# DIY_Keyboard_V1_4.net
KiCad netlist of a schematic drawn in EAGLE
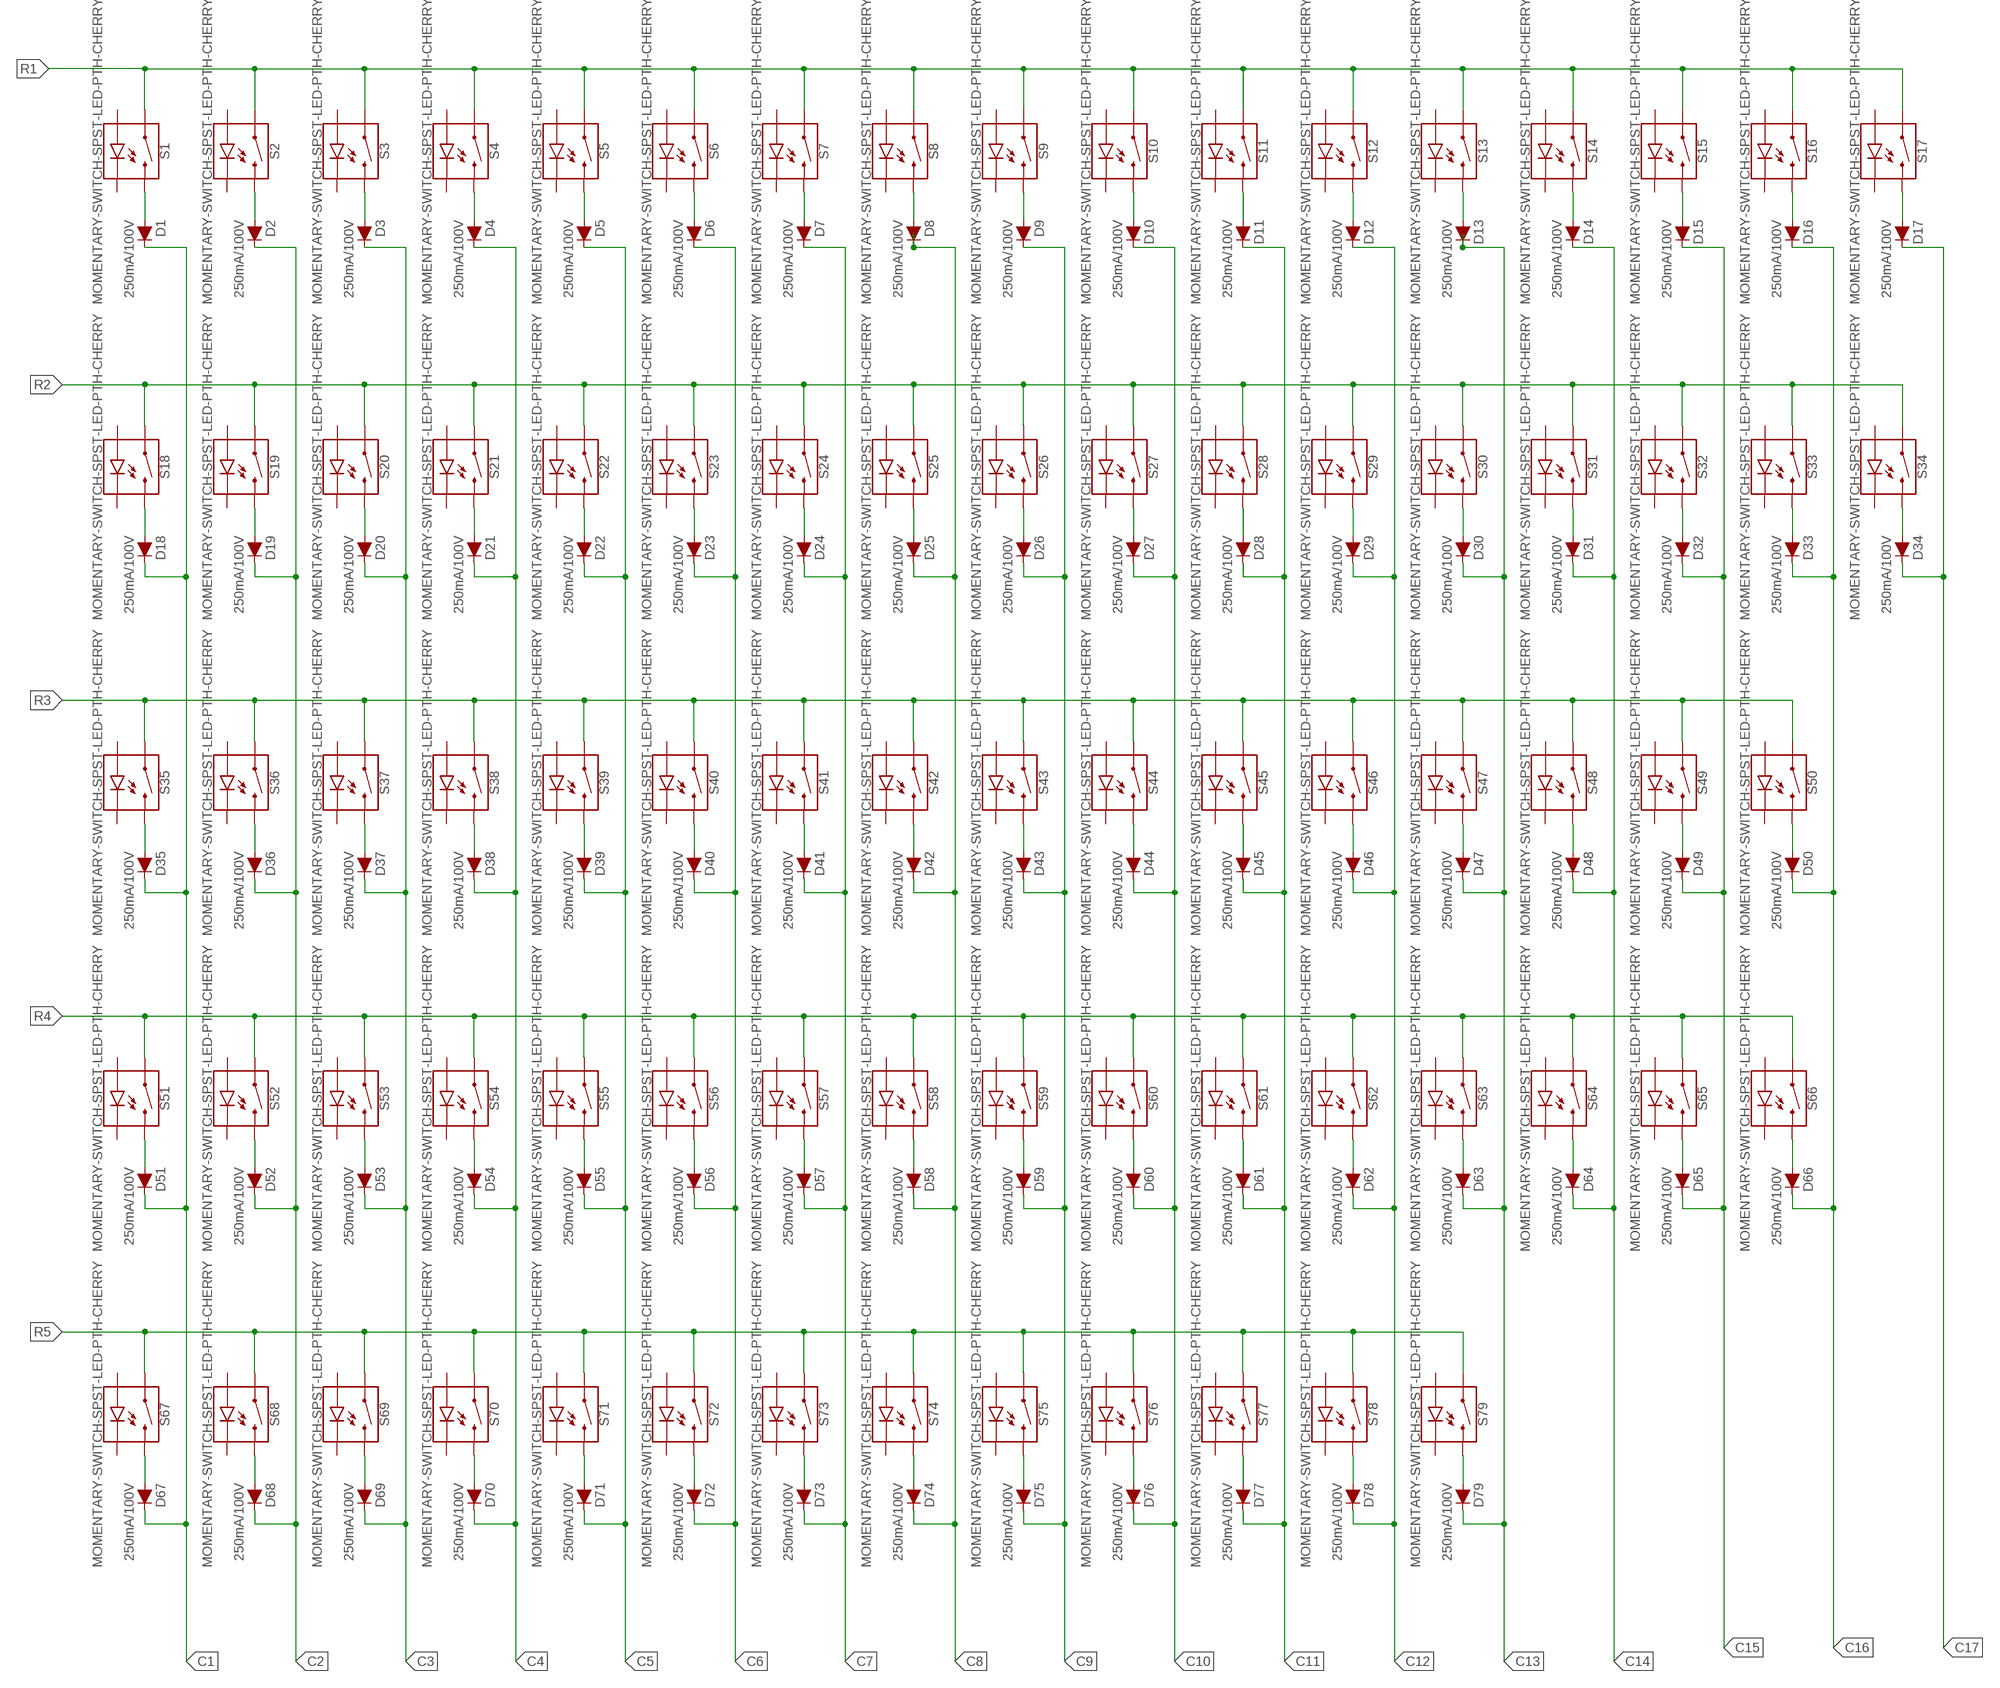
[diagram p0: schematic, sheet 1, part 1 of 2]
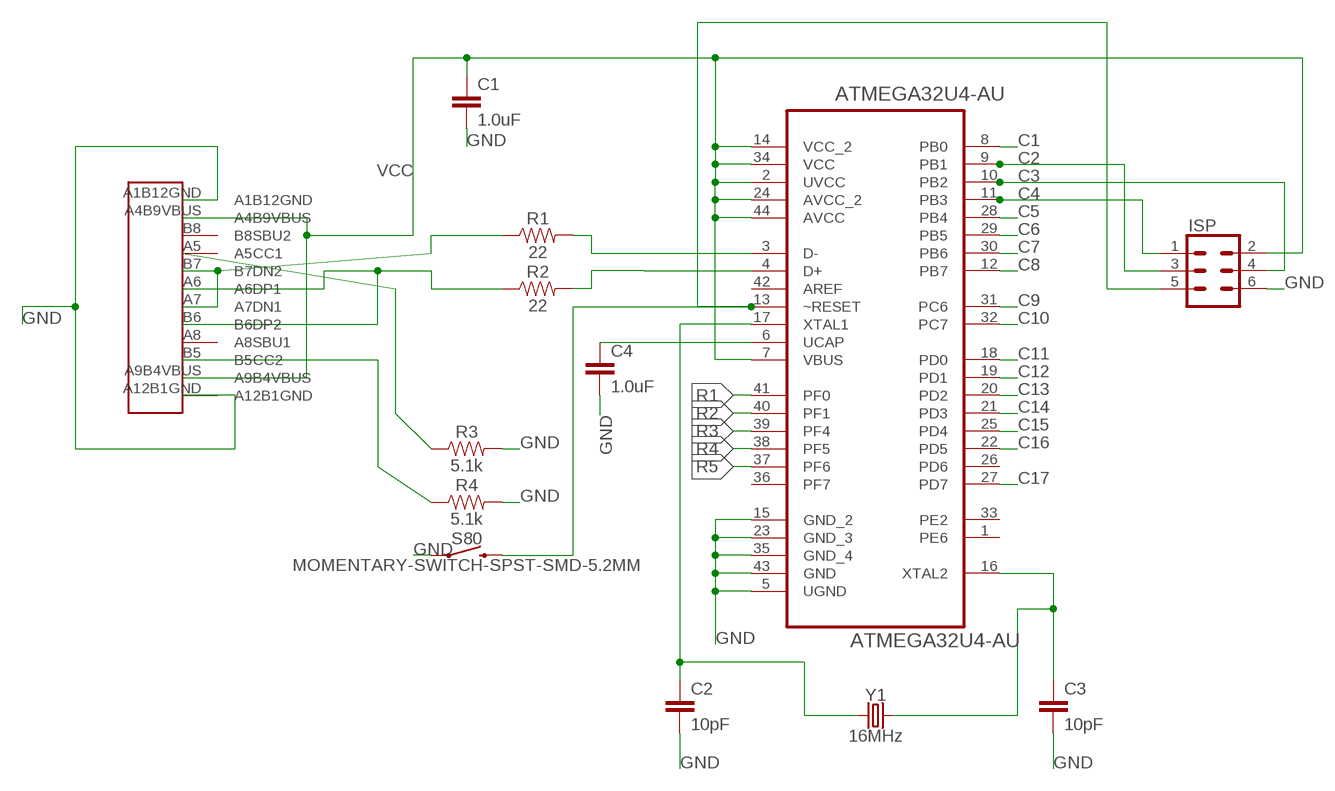
[diagram p1: schematic, sheet 1, part 2 of 2]

(export (version "E")
  (design (tool "Eeschema 10.0.6"))
  (components
    (comp (ref "ATMEGA32U4-AU")
      (value "ATMEGA32U4-AU")
      (footprint "eagle-import:QFP80P1200X1200X120-44N")
      (fields (field (name "MF") "Microchip"))
      (libsource (lib "eagle-import") (part "ATMEGA32U4-AU"))
    )
    (comp (ref "C1")
      (value "1.0uF")
      (footprint "eagle-import:0603")
      (libsource (lib "eagle-import") (part "1.0UF-0603-16V-10%"))
    )
    (comp (ref "C2")
      (value "10pF")
      (footprint "eagle-import:0603")
      (libsource (lib "eagle-import") (part "10PF-0603-50V-5%"))
    )
    (comp (ref "C3")
      (value "10pF")
      (footprint "eagle-import:0603")
      (libsource (lib "eagle-import") (part "10PF-0603-50V-5%"))
    )
    (comp (ref "C4")
      (value "1.0uF")
      (footprint "eagle-import:0603")
      (libsource (lib "eagle-import") (part "1.0UF-0603-16V-10%"))
    )
    (comp (ref "D1")
      (value "250mA/100V")
      (footprint "eagle-import:SOD-323")
      (libsource (lib "eagle-import") (part "DIODE-BAS16J"))
    )
    (comp (ref "D2")
      (value "250mA/100V")
      (footprint "eagle-import:SOD-323")
      (libsource (lib "eagle-import") (part "DIODE-BAS16J"))
    )
    (comp (ref "D3")
      (value "250mA/100V")
      (footprint "eagle-import:SOD-323")
      (libsource (lib "eagle-import") (part "DIODE-BAS16J"))
    )
    (comp (ref "D4")
      (value "250mA/100V")
      (footprint "eagle-import:SOD-323")
      (libsource (lib "eagle-import") (part "DIODE-BAS16J"))
    )
    (comp (ref "D5")
      (value "250mA/100V")
      (footprint "eagle-import:SOD-323")
      (libsource (lib "eagle-import") (part "DIODE-BAS16J"))
    )
    (comp (ref "D6")
      (value "250mA/100V")
      (footprint "eagle-import:SOD-323")
      (libsource (lib "eagle-import") (part "DIODE-BAS16J"))
    )
    (comp (ref "D7")
      (value "250mA/100V")
      (footprint "eagle-import:SOD-323")
      (libsource (lib "eagle-import") (part "DIODE-BAS16J"))
    )
    (comp (ref "D8")
      (value "250mA/100V")
      (footprint "eagle-import:SOD-323")
      (libsource (lib "eagle-import") (part "DIODE-BAS16J"))
    )
    (comp (ref "D9")
      (value "250mA/100V")
      (footprint "eagle-import:SOD-323")
      (libsource (lib "eagle-import") (part "DIODE-BAS16J"))
    )
    (comp (ref "D10")
      (value "250mA/100V")
      (footprint "eagle-import:SOD-323")
      (libsource (lib "eagle-import") (part "DIODE-BAS16J"))
    )
    (comp (ref "D11")
      (value "250mA/100V")
      (footprint "eagle-import:SOD-323")
      (libsource (lib "eagle-import") (part "DIODE-BAS16J"))
    )
    (comp (ref "D12")
      (value "250mA/100V")
      (footprint "eagle-import:SOD-323")
      (libsource (lib "eagle-import") (part "DIODE-BAS16J"))
    )
    (comp (ref "D13")
      (value "250mA/100V")
      (footprint "eagle-import:SOD-323")
      (libsource (lib "eagle-import") (part "DIODE-BAS16J"))
    )
    (comp (ref "D14")
      (value "250mA/100V")
      (footprint "eagle-import:SOD-323")
      (libsource (lib "eagle-import") (part "DIODE-BAS16J"))
    )
    (comp (ref "D15")
      (value "250mA/100V")
      (footprint "eagle-import:SOD-323")
      (libsource (lib "eagle-import") (part "DIODE-BAS16J"))
    )
    (comp (ref "D16")
      (value "250mA/100V")
      (footprint "eagle-import:SOD-323")
      (libsource (lib "eagle-import") (part "DIODE-BAS16J"))
    )
    (comp (ref "D17")
      (value "250mA/100V")
      (footprint "eagle-import:SOD-323")
      (libsource (lib "eagle-import") (part "DIODE-BAS16J"))
    )
    (comp (ref "D18")
      (value "250mA/100V")
      (footprint "eagle-import:SOD-323")
      (libsource (lib "eagle-import") (part "DIODE-BAS16J"))
    )
    (comp (ref "D19")
      (value "250mA/100V")
      (footprint "eagle-import:SOD-323")
      (libsource (lib "eagle-import") (part "DIODE-BAS16J"))
    )
    (comp (ref "D20")
      (value "250mA/100V")
      (footprint "eagle-import:SOD-323")
      (libsource (lib "eagle-import") (part "DIODE-BAS16J"))
    )
    (comp (ref "D21")
      (value "250mA/100V")
      (footprint "eagle-import:SOD-323")
      (libsource (lib "eagle-import") (part "DIODE-BAS16J"))
    )
    (comp (ref "D22")
      (value "250mA/100V")
      (footprint "eagle-import:SOD-323")
      (libsource (lib "eagle-import") (part "DIODE-BAS16J"))
    )
    (comp (ref "D23")
      (value "250mA/100V")
      (footprint "eagle-import:SOD-323")
      (libsource (lib "eagle-import") (part "DIODE-BAS16J"))
    )
    (comp (ref "D24")
      (value "250mA/100V")
      (footprint "eagle-import:SOD-323")
      (libsource (lib "eagle-import") (part "DIODE-BAS16J"))
    )
    (comp (ref "D25")
      (value "250mA/100V")
      (footprint "eagle-import:SOD-323")
      (libsource (lib "eagle-import") (part "DIODE-BAS16J"))
    )
    (comp (ref "D26")
      (value "250mA/100V")
      (footprint "eagle-import:SOD-323")
      (libsource (lib "eagle-import") (part "DIODE-BAS16J"))
    )
    (comp (ref "D27")
      (value "250mA/100V")
      (footprint "eagle-import:SOD-323")
      (libsource (lib "eagle-import") (part "DIODE-BAS16J"))
    )
    (comp (ref "D28")
      (value "250mA/100V")
      (footprint "eagle-import:SOD-323")
      (libsource (lib "eagle-import") (part "DIODE-BAS16J"))
    )
    (comp (ref "D29")
      (value "250mA/100V")
      (footprint "eagle-import:SOD-323")
      (libsource (lib "eagle-import") (part "DIODE-BAS16J"))
    )
    (comp (ref "D30")
      (value "250mA/100V")
      (footprint "eagle-import:SOD-323")
      (libsource (lib "eagle-import") (part "DIODE-BAS16J"))
    )
    (comp (ref "D31")
      (value "250mA/100V")
      (footprint "eagle-import:SOD-323")
      (libsource (lib "eagle-import") (part "DIODE-BAS16J"))
    )
    (comp (ref "D32")
      (value "250mA/100V")
      (footprint "eagle-import:SOD-323")
      (libsource (lib "eagle-import") (part "DIODE-BAS16J"))
    )
    (comp (ref "D33")
      (value "250mA/100V")
      (footprint "eagle-import:SOD-323")
      (libsource (lib "eagle-import") (part "DIODE-BAS16J"))
    )
    (comp (ref "D34")
      (value "250mA/100V")
      (footprint "eagle-import:SOD-323")
      (libsource (lib "eagle-import") (part "DIODE-BAS16J"))
    )
    (comp (ref "D35")
      (value "250mA/100V")
      (footprint "eagle-import:SOD-323")
      (libsource (lib "eagle-import") (part "DIODE-BAS16J"))
    )
    (comp (ref "D36")
      (value "250mA/100V")
      (footprint "eagle-import:SOD-323")
      (libsource (lib "eagle-import") (part "DIODE-BAS16J"))
    )
    (comp (ref "D37")
      (value "250mA/100V")
      (footprint "eagle-import:SOD-323")
      (libsource (lib "eagle-import") (part "DIODE-BAS16J"))
    )
    (comp (ref "D38")
      (value "250mA/100V")
      (footprint "eagle-import:SOD-323")
      (libsource (lib "eagle-import") (part "DIODE-BAS16J"))
    )
    (comp (ref "D39")
      (value "250mA/100V")
      (footprint "eagle-import:SOD-323")
      (libsource (lib "eagle-import") (part "DIODE-BAS16J"))
    )
    (comp (ref "D40")
      (value "250mA/100V")
      (footprint "eagle-import:SOD-323")
      (libsource (lib "eagle-import") (part "DIODE-BAS16J"))
    )
    (comp (ref "D41")
      (value "250mA/100V")
      (footprint "eagle-import:SOD-323")
      (libsource (lib "eagle-import") (part "DIODE-BAS16J"))
    )
    (comp (ref "D42")
      (value "250mA/100V")
      (footprint "eagle-import:SOD-323")
      (libsource (lib "eagle-import") (part "DIODE-BAS16J"))
    )
    (comp (ref "D43")
      (value "250mA/100V")
      (footprint "eagle-import:SOD-323")
      (libsource (lib "eagle-import") (part "DIODE-BAS16J"))
    )
    (comp (ref "D44")
      (value "250mA/100V")
      (footprint "eagle-import:SOD-323")
      (libsource (lib "eagle-import") (part "DIODE-BAS16J"))
    )
    (comp (ref "D45")
      (value "250mA/100V")
      (footprint "eagle-import:SOD-323")
      (libsource (lib "eagle-import") (part "DIODE-BAS16J"))
    )
    (comp (ref "D46")
      (value "250mA/100V")
      (footprint "eagle-import:SOD-323")
      (libsource (lib "eagle-import") (part "DIODE-BAS16J"))
    )
    (comp (ref "D47")
      (value "250mA/100V")
      (footprint "eagle-import:SOD-323")
      (libsource (lib "eagle-import") (part "DIODE-BAS16J"))
    )
    (comp (ref "D48")
      (value "250mA/100V")
      (footprint "eagle-import:SOD-323")
      (libsource (lib "eagle-import") (part "DIODE-BAS16J"))
    )
    (comp (ref "D49")
      (value "250mA/100V")
      (footprint "eagle-import:SOD-323")
      (libsource (lib "eagle-import") (part "DIODE-BAS16J"))
    )
    (comp (ref "D50")
      (value "250mA/100V")
      (footprint "eagle-import:SOD-323")
      (libsource (lib "eagle-import") (part "DIODE-BAS16J"))
    )
    (comp (ref "D51")
      (value "250mA/100V")
      (footprint "eagle-import:SOD-323")
      (libsource (lib "eagle-import") (part "DIODE-BAS16J"))
    )
    (comp (ref "D52")
      (value "250mA/100V")
      (footprint "eagle-import:SOD-323")
      (libsource (lib "eagle-import") (part "DIODE-BAS16J"))
    )
    (comp (ref "D53")
      (value "250mA/100V")
      (footprint "eagle-import:SOD-323")
      (libsource (lib "eagle-import") (part "DIODE-BAS16J"))
    )
    (comp (ref "D54")
      (value "250mA/100V")
      (footprint "eagle-import:SOD-323")
      (libsource (lib "eagle-import") (part "DIODE-BAS16J"))
    )
    (comp (ref "D55")
      (value "250mA/100V")
      (footprint "eagle-import:SOD-323")
      (libsource (lib "eagle-import") (part "DIODE-BAS16J"))
    )
    (comp (ref "D56")
      (value "250mA/100V")
      (footprint "eagle-import:SOD-323")
      (libsource (lib "eagle-import") (part "DIODE-BAS16J"))
    )
    (comp (ref "D57")
      (value "250mA/100V")
      (footprint "eagle-import:SOD-323")
      (libsource (lib "eagle-import") (part "DIODE-BAS16J"))
    )
    (comp (ref "D58")
      (value "250mA/100V")
      (footprint "eagle-import:SOD-323")
      (libsource (lib "eagle-import") (part "DIODE-BAS16J"))
    )
    (comp (ref "D59")
      (value "250mA/100V")
      (footprint "eagle-import:SOD-323")
      (libsource (lib "eagle-import") (part "DIODE-BAS16J"))
    )
    (comp (ref "D60")
      (value "250mA/100V")
      (footprint "eagle-import:SOD-323")
      (libsource (lib "eagle-import") (part "DIODE-BAS16J"))
    )
    (comp (ref "D61")
      (value "250mA/100V")
      (footprint "eagle-import:SOD-323")
      (libsource (lib "eagle-import") (part "DIODE-BAS16J"))
    )
    (comp (ref "D62")
      (value "250mA/100V")
      (footprint "eagle-import:SOD-323")
      (libsource (lib "eagle-import") (part "DIODE-BAS16J"))
    )
    (comp (ref "D63")
      (value "250mA/100V")
      (footprint "eagle-import:SOD-323")
      (libsource (lib "eagle-import") (part "DIODE-BAS16J"))
    )
    (comp (ref "D64")
      (value "250mA/100V")
      (footprint "eagle-import:SOD-323")
      (libsource (lib "eagle-import") (part "DIODE-BAS16J"))
    )
    (comp (ref "D65")
      (value "250mA/100V")
      (footprint "eagle-import:SOD-323")
      (libsource (lib "eagle-import") (part "DIODE-BAS16J"))
    )
    (comp (ref "D66")
      (value "250mA/100V")
      (footprint "eagle-import:SOD-323")
      (libsource (lib "eagle-import") (part "DIODE-BAS16J"))
    )
    (comp (ref "D67")
      (value "250mA/100V")
      (footprint "eagle-import:SOD-323")
      (libsource (lib "eagle-import") (part "DIODE-BAS16J"))
    )
    (comp (ref "D68")
      (value "250mA/100V")
      (footprint "eagle-import:SOD-323")
      (libsource (lib "eagle-import") (part "DIODE-BAS16J"))
    )
    (comp (ref "D69")
      (value "250mA/100V")
      (footprint "eagle-import:SOD-323")
      (libsource (lib "eagle-import") (part "DIODE-BAS16J"))
    )
    (comp (ref "D70")
      (value "250mA/100V")
      (footprint "eagle-import:SOD-323")
      (libsource (lib "eagle-import") (part "DIODE-BAS16J"))
    )
    (comp (ref "D71")
      (value "250mA/100V")
      (footprint "eagle-import:SOD-323")
      (libsource (lib "eagle-import") (part "DIODE-BAS16J"))
    )
    (comp (ref "D72")
      (value "250mA/100V")
      (footprint "eagle-import:SOD-323")
      (libsource (lib "eagle-import") (part "DIODE-BAS16J"))
    )
    (comp (ref "D73")
      (value "250mA/100V")
      (footprint "eagle-import:SOD-323")
      (libsource (lib "eagle-import") (part "DIODE-BAS16J"))
    )
    (comp (ref "D74")
      (value "250mA/100V")
      (footprint "eagle-import:SOD-323")
      (libsource (lib "eagle-import") (part "DIODE-BAS16J"))
    )
    (comp (ref "D75")
      (value "250mA/100V")
      (footprint "eagle-import:SOD-323")
      (libsource (lib "eagle-import") (part "DIODE-BAS16J"))
    )
    (comp (ref "D76")
      (value "250mA/100V")
      (footprint "eagle-import:SOD-323")
      (libsource (lib "eagle-import") (part "DIODE-BAS16J"))
    )
    (comp (ref "D77")
      (value "250mA/100V")
      (footprint "eagle-import:SOD-323")
      (libsource (lib "eagle-import") (part "DIODE-BAS16J"))
    )
    (comp (ref "D78")
      (value "250mA/100V")
      (footprint "eagle-import:SOD-323")
      (libsource (lib "eagle-import") (part "DIODE-BAS16J"))
    )
    (comp (ref "D79")
      (value "250mA/100V")
      (footprint "eagle-import:SOD-323")
      (libsource (lib "eagle-import") (part "DIODE-BAS16J"))
    )
    (comp (ref "ISP")
      (value "CONN_03X2FEMALE")
      (footprint "eagle-import:2X3")
      (libsource (lib "eagle-import") (part "CONN_03X2FEMALE"))
    )
    (comp (ref "R1")
      (value "22")
      (footprint "eagle-import:0603")
      (libsource (lib "eagle-import") (part "22OHM-0603-1/10W-1%"))
    )
    (comp (ref "R2")
      (value "22")
      (footprint "eagle-import:0603")
      (libsource (lib "eagle-import") (part "22OHM-0603-1/10W-1%"))
    )
    (comp (ref "R3")
      (value "5.1k")
      (footprint "eagle-import:0603")
      (libsource (lib "eagle-import") (part "56KOHM"))
    )
    (comp (ref "R4")
      (value "5.1k")
      (footprint "eagle-import:0603")
      (libsource (lib "eagle-import") (part "56KOHM"))
    )
    (comp (ref "S1")
      (value "MOMENTARY-SWITCH-SPST-LED-PTH-CHERRY")
      (footprint "eagle-import:CHERRY-MX-LED")
      (libsource (lib "eagle-import") (part "MOMENTARY-SWITCH-SPST-LED-PTH-CHERRY"))
    )
    (comp (ref "S2")
      (value "MOMENTARY-SWITCH-SPST-LED-PTH-CHERRY")
      (footprint "eagle-import:CHERRY-MX-LED")
      (libsource (lib "eagle-import") (part "MOMENTARY-SWITCH-SPST-LED-PTH-CHERRY"))
    )
    (comp (ref "S3")
      (value "MOMENTARY-SWITCH-SPST-LED-PTH-CHERRY")
      (footprint "eagle-import:CHERRY-MX-LED")
      (libsource (lib "eagle-import") (part "MOMENTARY-SWITCH-SPST-LED-PTH-CHERRY"))
    )
    (comp (ref "S4")
      (value "MOMENTARY-SWITCH-SPST-LED-PTH-CHERRY")
      (footprint "eagle-import:CHERRY-MX-LED")
      (libsource (lib "eagle-import") (part "MOMENTARY-SWITCH-SPST-LED-PTH-CHERRY"))
    )
    (comp (ref "S5")
      (value "MOMENTARY-SWITCH-SPST-LED-PTH-CHERRY")
      (footprint "eagle-import:CHERRY-MX-LED")
      (libsource (lib "eagle-import") (part "MOMENTARY-SWITCH-SPST-LED-PTH-CHERRY"))
    )
    (comp (ref "S6")
      (value "MOMENTARY-SWITCH-SPST-LED-PTH-CHERRY")
      (footprint "eagle-import:CHERRY-MX-LED")
      (libsource (lib "eagle-import") (part "MOMENTARY-SWITCH-SPST-LED-PTH-CHERRY"))
    )
    (comp (ref "S7")
      (value "MOMENTARY-SWITCH-SPST-LED-PTH-CHERRY")
      (footprint "eagle-import:CHERRY-MX-LED")
      (libsource (lib "eagle-import") (part "MOMENTARY-SWITCH-SPST-LED-PTH-CHERRY"))
    )
    (comp (ref "S8")
      (value "MOMENTARY-SWITCH-SPST-LED-PTH-CHERRY")
      (footprint "eagle-import:CHERRY-MX-LED")
      (libsource (lib "eagle-import") (part "MOMENTARY-SWITCH-SPST-LED-PTH-CHERRY"))
    )
    (comp (ref "S9")
      (value "MOMENTARY-SWITCH-SPST-LED-PTH-CHERRY")
      (footprint "eagle-import:CHERRY-MX-LED")
      (libsource (lib "eagle-import") (part "MOMENTARY-SWITCH-SPST-LED-PTH-CHERRY"))
    )
    (comp (ref "S10")
      (value "MOMENTARY-SWITCH-SPST-LED-PTH-CHERRY")
      (footprint "eagle-import:CHERRY-MX-LED")
      (libsource (lib "eagle-import") (part "MOMENTARY-SWITCH-SPST-LED-PTH-CHERRY"))
    )
    (comp (ref "S11")
      (value "MOMENTARY-SWITCH-SPST-LED-PTH-CHERRY")
      (footprint "eagle-import:CHERRY-MX-LED")
      (libsource (lib "eagle-import") (part "MOMENTARY-SWITCH-SPST-LED-PTH-CHERRY"))
    )
    (comp (ref "S12")
      (value "MOMENTARY-SWITCH-SPST-LED-PTH-CHERRY")
      (footprint "eagle-import:CHERRY-MX-LED")
      (libsource (lib "eagle-import") (part "MOMENTARY-SWITCH-SPST-LED-PTH-CHERRY"))
    )
    (comp (ref "S13")
      (value "MOMENTARY-SWITCH-SPST-LED-PTH-CHERRY")
      (footprint "eagle-import:CHERRY-MX-LED")
      (libsource (lib "eagle-import") (part "MOMENTARY-SWITCH-SPST-LED-PTH-CHERRY"))
    )
    (comp (ref "S14")
      (value "MOMENTARY-SWITCH-SPST-LED-PTH-CHERRY")
      (footprint "eagle-import:CHERRY-MX-LED")
      (libsource (lib "eagle-import") (part "MOMENTARY-SWITCH-SPST-LED-PTH-CHERRY"))
    )
    (comp (ref "S15")
      (value "MOMENTARY-SWITCH-SPST-LED-PTH-CHERRY")
      (footprint "eagle-import:CHERRY-MX-LED")
      (libsource (lib "eagle-import") (part "MOMENTARY-SWITCH-SPST-LED-PTH-CHERRY"))
    )
    (comp (ref "S16")
      (value "MOMENTARY-SWITCH-SPST-LED-PTH-CHERRY")
      (footprint "eagle-import:CHERRY-MX-LED")
      (libsource (lib "eagle-import") (part "MOMENTARY-SWITCH-SPST-LED-PTH-CHERRY"))
    )
    (comp (ref "S17")
      (value "MOMENTARY-SWITCH-SPST-LED-PTH-CHERRY")
      (footprint "eagle-import:CHERRY-MX-LED")
      (libsource (lib "eagle-import") (part "MOMENTARY-SWITCH-SPST-LED-PTH-CHERRY"))
    )
    (comp (ref "S18")
      (value "MOMENTARY-SWITCH-SPST-LED-PTH-CHERRY")
      (footprint "eagle-import:CHERRY-MX-LED")
      (libsource (lib "eagle-import") (part "MOMENTARY-SWITCH-SPST-LED-PTH-CHERRY"))
    )
    (comp (ref "S19")
      (value "MOMENTARY-SWITCH-SPST-LED-PTH-CHERRY")
      (footprint "eagle-import:CHERRY-MX-LED")
      (libsource (lib "eagle-import") (part "MOMENTARY-SWITCH-SPST-LED-PTH-CHERRY"))
    )
    (comp (ref "S20")
      (value "MOMENTARY-SWITCH-SPST-LED-PTH-CHERRY")
      (footprint "eagle-import:CHERRY-MX-LED")
      (libsource (lib "eagle-import") (part "MOMENTARY-SWITCH-SPST-LED-PTH-CHERRY"))
    )
    (comp (ref "S21")
      (value "MOMENTARY-SWITCH-SPST-LED-PTH-CHERRY")
      (footprint "eagle-import:CHERRY-MX-LED")
      (libsource (lib "eagle-import") (part "MOMENTARY-SWITCH-SPST-LED-PTH-CHERRY"))
    )
    (comp (ref "S22")
      (value "MOMENTARY-SWITCH-SPST-LED-PTH-CHERRY")
      (footprint "eagle-import:CHERRY-MX-LED")
      (libsource (lib "eagle-import") (part "MOMENTARY-SWITCH-SPST-LED-PTH-CHERRY"))
    )
    (comp (ref "S23")
      (value "MOMENTARY-SWITCH-SPST-LED-PTH-CHERRY")
      (footprint "eagle-import:CHERRY-MX-LED")
      (libsource (lib "eagle-import") (part "MOMENTARY-SWITCH-SPST-LED-PTH-CHERRY"))
    )
    (comp (ref "S24")
      (value "MOMENTARY-SWITCH-SPST-LED-PTH-CHERRY")
      (footprint "eagle-import:CHERRY-MX-LED")
      (libsource (lib "eagle-import") (part "MOMENTARY-SWITCH-SPST-LED-PTH-CHERRY"))
    )
    (comp (ref "S25")
      (value "MOMENTARY-SWITCH-SPST-LED-PTH-CHERRY")
      (footprint "eagle-import:CHERRY-MX-LED")
      (libsource (lib "eagle-import") (part "MOMENTARY-SWITCH-SPST-LED-PTH-CHERRY"))
    )
    (comp (ref "S26")
      (value "MOMENTARY-SWITCH-SPST-LED-PTH-CHERRY")
      (footprint "eagle-import:CHERRY-MX-LED")
      (libsource (lib "eagle-import") (part "MOMENTARY-SWITCH-SPST-LED-PTH-CHERRY"))
    )
    (comp (ref "S27")
      (value "MOMENTARY-SWITCH-SPST-LED-PTH-CHERRY")
      (footprint "eagle-import:CHERRY-MX-LED")
      (libsource (lib "eagle-import") (part "MOMENTARY-SWITCH-SPST-LED-PTH-CHERRY"))
    )
    (comp (ref "S28")
      (value "MOMENTARY-SWITCH-SPST-LED-PTH-CHERRY")
      (footprint "eagle-import:CHERRY-MX-LED")
      (libsource (lib "eagle-import") (part "MOMENTARY-SWITCH-SPST-LED-PTH-CHERRY"))
    )
    (comp (ref "S29")
      (value "MOMENTARY-SWITCH-SPST-LED-PTH-CHERRY")
      (footprint "eagle-import:CHERRY-MX-LED")
      (libsource (lib "eagle-import") (part "MOMENTARY-SWITCH-SPST-LED-PTH-CHERRY"))
    )
    (comp (ref "S30")
      (value "MOMENTARY-SWITCH-SPST-LED-PTH-CHERRY")
      (footprint "eagle-import:CHERRY-MX-LED")
      (libsource (lib "eagle-import") (part "MOMENTARY-SWITCH-SPST-LED-PTH-CHERRY"))
    )
    (comp (ref "S31")
      (value "MOMENTARY-SWITCH-SPST-LED-PTH-CHERRY")
      (footprint "eagle-import:CHERRY-MX-LED")
      (libsource (lib "eagle-import") (part "MOMENTARY-SWITCH-SPST-LED-PTH-CHERRY"))
    )
    (comp (ref "S32")
      (value "MOMENTARY-SWITCH-SPST-LED-PTH-CHERRY")
      (footprint "eagle-import:CHERRY-MX-LED")
      (libsource (lib "eagle-import") (part "MOMENTARY-SWITCH-SPST-LED-PTH-CHERRY"))
    )
    (comp (ref "S33")
      (value "MOMENTARY-SWITCH-SPST-LED-PTH-CHERRY")
      (footprint "eagle-import:CHERRY-MX-LED")
      (libsource (lib "eagle-import") (part "MOMENTARY-SWITCH-SPST-LED-PTH-CHERRY"))
    )
    (comp (ref "S34")
      (value "MOMENTARY-SWITCH-SPST-LED-PTH-CHERRY")
      (footprint "eagle-import:CHERRY-MX-LED")
      (libsource (lib "eagle-import") (part "MOMENTARY-SWITCH-SPST-LED-PTH-CHERRY"))
    )
    (comp (ref "S35")
      (value "MOMENTARY-SWITCH-SPST-LED-PTH-CHERRY")
      (footprint "eagle-import:CHERRY-MX-LED")
      (libsource (lib "eagle-import") (part "MOMENTARY-SWITCH-SPST-LED-PTH-CHERRY"))
    )
    (comp (ref "S36")
      (value "MOMENTARY-SWITCH-SPST-LED-PTH-CHERRY")
      (footprint "eagle-import:CHERRY-MX-LED")
      (libsource (lib "eagle-import") (part "MOMENTARY-SWITCH-SPST-LED-PTH-CHERRY"))
    )
    (comp (ref "S37")
      (value "MOMENTARY-SWITCH-SPST-LED-PTH-CHERRY")
      (footprint "eagle-import:CHERRY-MX-LED")
      (libsource (lib "eagle-import") (part "MOMENTARY-SWITCH-SPST-LED-PTH-CHERRY"))
    )
    (comp (ref "S38")
      (value "MOMENTARY-SWITCH-SPST-LED-PTH-CHERRY")
      (footprint "eagle-import:CHERRY-MX-LED")
      (libsource (lib "eagle-import") (part "MOMENTARY-SWITCH-SPST-LED-PTH-CHERRY"))
    )
    (comp (ref "S39")
      (value "MOMENTARY-SWITCH-SPST-LED-PTH-CHERRY")
      (footprint "eagle-import:CHERRY-MX-LED")
      (libsource (lib "eagle-import") (part "MOMENTARY-SWITCH-SPST-LED-PTH-CHERRY"))
    )
    (comp (ref "S40")
      (value "MOMENTARY-SWITCH-SPST-LED-PTH-CHERRY")
      (footprint "eagle-import:CHERRY-MX-LED")
      (libsource (lib "eagle-import") (part "MOMENTARY-SWITCH-SPST-LED-PTH-CHERRY"))
    )
    (comp (ref "S41")
      (value "MOMENTARY-SWITCH-SPST-LED-PTH-CHERRY")
      (footprint "eagle-import:CHERRY-MX-LED")
      (libsource (lib "eagle-import") (part "MOMENTARY-SWITCH-SPST-LED-PTH-CHERRY"))
    )
    (comp (ref "S42")
      (value "MOMENTARY-SWITCH-SPST-LED-PTH-CHERRY")
      (footprint "eagle-import:CHERRY-MX-LED")
      (libsource (lib "eagle-import") (part "MOMENTARY-SWITCH-SPST-LED-PTH-CHERRY"))
    )
    (comp (ref "S43")
      (value "MOMENTARY-SWITCH-SPST-LED-PTH-CHERRY")
      (footprint "eagle-import:CHERRY-MX-LED")
      (libsource (lib "eagle-import") (part "MOMENTARY-SWITCH-SPST-LED-PTH-CHERRY"))
    )
    (comp (ref "S44")
      (value "MOMENTARY-SWITCH-SPST-LED-PTH-CHERRY")
      (footprint "eagle-import:CHERRY-MX-LED")
      (libsource (lib "eagle-import") (part "MOMENTARY-SWITCH-SPST-LED-PTH-CHERRY"))
    )
    (comp (ref "S45")
      (value "MOMENTARY-SWITCH-SPST-LED-PTH-CHERRY")
      (footprint "eagle-import:CHERRY-MX-LED")
      (libsource (lib "eagle-import") (part "MOMENTARY-SWITCH-SPST-LED-PTH-CHERRY"))
    )
    (comp (ref "S46")
      (value "MOMENTARY-SWITCH-SPST-LED-PTH-CHERRY")
      (footprint "eagle-import:CHERRY-MX-LED")
      (libsource (lib "eagle-import") (part "MOMENTARY-SWITCH-SPST-LED-PTH-CHERRY"))
    )
    (comp (ref "S47")
      (value "MOMENTARY-SWITCH-SPST-LED-PTH-CHERRY")
      (footprint "eagle-import:CHERRY-MX-LED")
      (libsource (lib "eagle-import") (part "MOMENTARY-SWITCH-SPST-LED-PTH-CHERRY"))
    )
    (comp (ref "S48")
      (value "MOMENTARY-SWITCH-SPST-LED-PTH-CHERRY")
      (footprint "eagle-import:CHERRY-MX-LED")
      (libsource (lib "eagle-import") (part "MOMENTARY-SWITCH-SPST-LED-PTH-CHERRY"))
    )
    (comp (ref "S49")
      (value "MOMENTARY-SWITCH-SPST-LED-PTH-CHERRY")
      (footprint "eagle-import:CHERRY-MX-LED")
      (libsource (lib "eagle-import") (part "MOMENTARY-SWITCH-SPST-LED-PTH-CHERRY"))
    )
    (comp (ref "S50")
      (value "MOMENTARY-SWITCH-SPST-LED-PTH-CHERRY")
      (footprint "eagle-import:CHERRY-MX-LED")
      (libsource (lib "eagle-import") (part "MOMENTARY-SWITCH-SPST-LED-PTH-CHERRY"))
    )
    (comp (ref "S51")
      (value "MOMENTARY-SWITCH-SPST-LED-PTH-CHERRY")
      (footprint "eagle-import:CHERRY-MX-LED")
      (libsource (lib "eagle-import") (part "MOMENTARY-SWITCH-SPST-LED-PTH-CHERRY"))
    )
    (comp (ref "S52")
      (value "MOMENTARY-SWITCH-SPST-LED-PTH-CHERRY")
      (footprint "eagle-import:CHERRY-MX-LED")
      (libsource (lib "eagle-import") (part "MOMENTARY-SWITCH-SPST-LED-PTH-CHERRY"))
    )
    (comp (ref "S53")
      (value "MOMENTARY-SWITCH-SPST-LED-PTH-CHERRY")
      (footprint "eagle-import:CHERRY-MX-LED")
      (libsource (lib "eagle-import") (part "MOMENTARY-SWITCH-SPST-LED-PTH-CHERRY"))
    )
    (comp (ref "S54")
      (value "MOMENTARY-SWITCH-SPST-LED-PTH-CHERRY")
      (footprint "eagle-import:CHERRY-MX-LED")
      (libsource (lib "eagle-import") (part "MOMENTARY-SWITCH-SPST-LED-PTH-CHERRY"))
    )
    (comp (ref "S55")
      (value "MOMENTARY-SWITCH-SPST-LED-PTH-CHERRY")
      (footprint "eagle-import:CHERRY-MX-LED")
      (libsource (lib "eagle-import") (part "MOMENTARY-SWITCH-SPST-LED-PTH-CHERRY"))
    )
    (comp (ref "S56")
      (value "MOMENTARY-SWITCH-SPST-LED-PTH-CHERRY")
      (footprint "eagle-import:CHERRY-MX-LED")
      (libsource (lib "eagle-import") (part "MOMENTARY-SWITCH-SPST-LED-PTH-CHERRY"))
    )
    (comp (ref "S57")
      (value "MOMENTARY-SWITCH-SPST-LED-PTH-CHERRY")
      (footprint "eagle-import:CHERRY-MX-LED")
      (libsource (lib "eagle-import") (part "MOMENTARY-SWITCH-SPST-LED-PTH-CHERRY"))
    )
    (comp (ref "S58")
      (value "MOMENTARY-SWITCH-SPST-LED-PTH-CHERRY")
      (footprint "eagle-import:CHERRY-MX-LED")
      (libsource (lib "eagle-import") (part "MOMENTARY-SWITCH-SPST-LED-PTH-CHERRY"))
    )
    (comp (ref "S59")
      (value "MOMENTARY-SWITCH-SPST-LED-PTH-CHERRY")
      (footprint "eagle-import:CHERRY-MX-LED")
      (libsource (lib "eagle-import") (part "MOMENTARY-SWITCH-SPST-LED-PTH-CHERRY"))
    )
    (comp (ref "S60")
      (value "MOMENTARY-SWITCH-SPST-LED-PTH-CHERRY")
      (footprint "eagle-import:CHERRY-MX-LED")
      (libsource (lib "eagle-import") (part "MOMENTARY-SWITCH-SPST-LED-PTH-CHERRY"))
    )
    (comp (ref "S61")
      (value "MOMENTARY-SWITCH-SPST-LED-PTH-CHERRY")
      (footprint "eagle-import:CHERRY-MX-LED")
      (libsource (lib "eagle-import") (part "MOMENTARY-SWITCH-SPST-LED-PTH-CHERRY"))
    )
    (comp (ref "S62")
      (value "MOMENTARY-SWITCH-SPST-LED-PTH-CHERRY")
      (footprint "eagle-import:CHERRY-MX-LED")
      (libsource (lib "eagle-import") (part "MOMENTARY-SWITCH-SPST-LED-PTH-CHERRY"))
    )
    (comp (ref "S63")
      (value "MOMENTARY-SWITCH-SPST-LED-PTH-CHERRY")
      (footprint "eagle-import:CHERRY-MX-LED")
      (libsource (lib "eagle-import") (part "MOMENTARY-SWITCH-SPST-LED-PTH-CHERRY"))
    )
    (comp (ref "S64")
      (value "MOMENTARY-SWITCH-SPST-LED-PTH-CHERRY")
      (footprint "eagle-import:CHERRY-MX-LED")
      (libsource (lib "eagle-import") (part "MOMENTARY-SWITCH-SPST-LED-PTH-CHERRY"))
    )
    (comp (ref "S65")
      (value "MOMENTARY-SWITCH-SPST-LED-PTH-CHERRY")
      (footprint "eagle-import:CHERRY-MX-LED")
      (libsource (lib "eagle-import") (part "MOMENTARY-SWITCH-SPST-LED-PTH-CHERRY"))
    )
    (comp (ref "S66")
      (value "MOMENTARY-SWITCH-SPST-LED-PTH-CHERRY")
      (footprint "eagle-import:CHERRY-MX-LED")
      (libsource (lib "eagle-import") (part "MOMENTARY-SWITCH-SPST-LED-PTH-CHERRY"))
    )
    (comp (ref "S67")
      (value "MOMENTARY-SWITCH-SPST-LED-PTH-CHERRY")
      (footprint "eagle-import:CHERRY-MX-LED")
      (libsource (lib "eagle-import") (part "MOMENTARY-SWITCH-SPST-LED-PTH-CHERRY"))
    )
    (comp (ref "S68")
      (value "MOMENTARY-SWITCH-SPST-LED-PTH-CHERRY")
      (footprint "eagle-import:CHERRY-MX-LED")
      (libsource (lib "eagle-import") (part "MOMENTARY-SWITCH-SPST-LED-PTH-CHERRY"))
    )
    (comp (ref "S69")
      (value "MOMENTARY-SWITCH-SPST-LED-PTH-CHERRY")
      (footprint "eagle-import:CHERRY-MX-LED")
      (libsource (lib "eagle-import") (part "MOMENTARY-SWITCH-SPST-LED-PTH-CHERRY"))
    )
    (comp (ref "S70")
      (value "MOMENTARY-SWITCH-SPST-LED-PTH-CHERRY")
      (footprint "eagle-import:CHERRY-MX-LED")
      (libsource (lib "eagle-import") (part "MOMENTARY-SWITCH-SPST-LED-PTH-CHERRY"))
    )
    (comp (ref "S71")
      (value "MOMENTARY-SWITCH-SPST-LED-PTH-CHERRY")
      (footprint "eagle-import:CHERRY-MX-LED")
      (libsource (lib "eagle-import") (part "MOMENTARY-SWITCH-SPST-LED-PTH-CHERRY"))
    )
    (comp (ref "S72")
      (value "MOMENTARY-SWITCH-SPST-LED-PTH-CHERRY")
      (footprint "eagle-import:CHERRY-MX-LED")
      (libsource (lib "eagle-import") (part "MOMENTARY-SWITCH-SPST-LED-PTH-CHERRY"))
    )
    (comp (ref "S73")
      (value "MOMENTARY-SWITCH-SPST-LED-PTH-CHERRY")
      (footprint "eagle-import:CHERRY-MX-LED")
      (libsource (lib "eagle-import") (part "MOMENTARY-SWITCH-SPST-LED-PTH-CHERRY"))
    )
    (comp (ref "S74")
      (value "MOMENTARY-SWITCH-SPST-LED-PTH-CHERRY")
      (footprint "eagle-import:CHERRY-MX-LED")
      (libsource (lib "eagle-import") (part "MOMENTARY-SWITCH-SPST-LED-PTH-CHERRY"))
    )
    (comp (ref "S75")
      (value "MOMENTARY-SWITCH-SPST-LED-PTH-CHERRY")
      (footprint "eagle-import:CHERRY-MX-LED")
      (libsource (lib "eagle-import") (part "MOMENTARY-SWITCH-SPST-LED-PTH-CHERRY"))
    )
    (comp (ref "S76")
      (value "MOMENTARY-SWITCH-SPST-LED-PTH-CHERRY")
      (footprint "eagle-import:CHERRY-MX-LED")
      (libsource (lib "eagle-import") (part "MOMENTARY-SWITCH-SPST-LED-PTH-CHERRY"))
    )
    (comp (ref "S77")
      (value "MOMENTARY-SWITCH-SPST-LED-PTH-CHERRY")
      (footprint "eagle-import:CHERRY-MX-LED")
      (libsource (lib "eagle-import") (part "MOMENTARY-SWITCH-SPST-LED-PTH-CHERRY"))
    )
    (comp (ref "S78")
      (value "MOMENTARY-SWITCH-SPST-LED-PTH-CHERRY")
      (footprint "eagle-import:CHERRY-MX-LED")
      (libsource (lib "eagle-import") (part "MOMENTARY-SWITCH-SPST-LED-PTH-CHERRY"))
    )
    (comp (ref "S79")
      (value "MOMENTARY-SWITCH-SPST-LED-PTH-CHERRY")
      (footprint "eagle-import:CHERRY-MX-LED")
      (libsource (lib "eagle-import") (part "MOMENTARY-SWITCH-SPST-LED-PTH-CHERRY"))
    )
    (comp (ref "S80")
      (value "MOMENTARY-SWITCH-SPST-SMD-5.2MM")
      (footprint "eagle-import:TACTILE_SWITCH_SMD_5.2MM")
      (libsource (lib "eagle-import") (part "MOMENTARY-SWITCH-SPST-SMD-5.2MM"))
    )
    (comp (ref "U$1")
      (value "USB_TYPE_C")
      (footprint "eagle-import:USB_TYPE_C")
      (libsource (lib "eagle-import") (part "USB_TYPE_C"))
    )
    (comp (ref "Y1")
      (value "16MHz")
      (footprint "eagle-import:CRYSTAL-SMD-5X3.2-4PAD")
      (libsource (lib "eagle-import") (part "CRYSTAL-16MHZSMD-5X3.2"))
    )
  )
  (nets
    (net (code "1") (name "/GND") (class "Default")
      (node (ref "ATMEGA32U4-AU") (pin "15") (pinfunction "GND_2_15") (pintype "passive"))
      (node (ref "ATMEGA32U4-AU") (pin "23") (pinfunction "GND_3_23") (pintype "passive"))
      (node (ref "ATMEGA32U4-AU") (pin "35") (pinfunction "GND_4_35") (pintype "passive"))
      (node (ref "ATMEGA32U4-AU") (pin "43") (pinfunction "GND_43") (pintype "passive"))
      (node (ref "ATMEGA32U4-AU") (pin "5") (pinfunction "UGND_5") (pintype "passive"))
      (node (ref "C1") (pin "2") (pinfunction "2_2") (pintype "passive"))
      (node (ref "C2") (pin "2") (pinfunction "2_2") (pintype "passive"))
      (node (ref "C3") (pin "2") (pinfunction "2_2") (pintype "passive"))
      (node (ref "C4") (pin "2") (pinfunction "2_2") (pintype "passive"))
      (node (ref "ISP") (pin "6") (pinfunction "6_6") (pintype "bidirectional"))
      (node (ref "R3") (pin "2") (pinfunction "2_2") (pintype "passive"))
      (node (ref "R4") (pin "2") (pinfunction "2_2") (pintype "passive"))
      (node (ref "S80") (pin "1") (pinfunction "1_1") (pintype "passive"))
      (node (ref "U$1") (pin "A12B1GND") (pinfunction "A12B1GND_A12B1GND") (pintype "bidirectional"))
      (node (ref "U$1") (pin "A1B12GND") (pinfunction "A1B12GND_A1B12GND") (pintype "bidirectional"))
    )
    (net (code "2") (name "/VCC") (class "Default")
      (node (ref "ATMEGA32U4-AU") (pin "14") (pinfunction "VCC_2_14") (pintype "power_in"))
      (node (ref "ATMEGA32U4-AU") (pin "2") (pinfunction "UVCC_2") (pintype "power_in"))
      (node (ref "ATMEGA32U4-AU") (pin "24") (pinfunction "AVCC_2_24") (pintype "power_in"))
      (node (ref "ATMEGA32U4-AU") (pin "34") (pinfunction "VCC_34") (pintype "power_in"))
      (node (ref "ATMEGA32U4-AU") (pin "44") (pinfunction "AVCC_44") (pintype "power_in"))
      (node (ref "ATMEGA32U4-AU") (pin "7") (pinfunction "VBUS_7") (pintype "input"))
      (node (ref "C1") (pin "1") (pinfunction "1_1") (pintype "passive"))
      (node (ref "ISP") (pin "2") (pinfunction "2_2") (pintype "bidirectional"))
      (node (ref "U$1") (pin "A4B9VBUS") (pinfunction "A4B9VBUS_A4B9VBUS") (pintype "bidirectional"))
      (node (ref "U$1") (pin "A9B4VBUS") (pinfunction "A9B4VBUS_A9B4VBUS") (pintype "bidirectional"))
    )
    (net (code "3") (name "C1") (class "Default")
      (node (ref "ATMEGA32U4-AU") (pin "8") (pinfunction "PB0_8") (pintype "bidirectional"))
      (node (ref "D1") (pin "C") (pinfunction "C_C") (pintype "passive"))
      (node (ref "D18") (pin "C") (pinfunction "C_C") (pintype "passive"))
      (node (ref "D35") (pin "C") (pinfunction "C_C") (pintype "passive"))
      (node (ref "D51") (pin "C") (pinfunction "C_C") (pintype "passive"))
      (node (ref "D67") (pin "C") (pinfunction "C_C") (pintype "passive"))
    )
    (net (code "4") (name "C2") (class "Default")
      (node (ref "ATMEGA32U4-AU") (pin "9") (pinfunction "PB1_9") (pintype "bidirectional"))
      (node (ref "D19") (pin "C") (pinfunction "C_C") (pintype "passive"))
      (node (ref "D2") (pin "C") (pinfunction "C_C") (pintype "passive"))
      (node (ref "D36") (pin "C") (pinfunction "C_C") (pintype "passive"))
      (node (ref "D52") (pin "C") (pinfunction "C_C") (pintype "passive"))
      (node (ref "D68") (pin "C") (pinfunction "C_C") (pintype "passive"))
      (node (ref "ISP") (pin "3") (pinfunction "3_3") (pintype "bidirectional"))
    )
    (net (code "5") (name "C3") (class "Default")
      (node (ref "ATMEGA32U4-AU") (pin "10") (pinfunction "PB2_10") (pintype "bidirectional"))
      (node (ref "D20") (pin "C") (pinfunction "C_C") (pintype "passive"))
      (node (ref "D3") (pin "C") (pinfunction "C_C") (pintype "passive"))
      (node (ref "D37") (pin "C") (pinfunction "C_C") (pintype "passive"))
      (node (ref "D53") (pin "C") (pinfunction "C_C") (pintype "passive"))
      (node (ref "D69") (pin "C") (pinfunction "C_C") (pintype "passive"))
      (node (ref "ISP") (pin "4") (pinfunction "4_4") (pintype "bidirectional"))
    )
    (net (code "6") (name "C4") (class "Default")
      (node (ref "ATMEGA32U4-AU") (pin "11") (pinfunction "PB3_11") (pintype "bidirectional"))
      (node (ref "D21") (pin "C") (pinfunction "C_C") (pintype "passive"))
      (node (ref "D38") (pin "C") (pinfunction "C_C") (pintype "passive"))
      (node (ref "D4") (pin "C") (pinfunction "C_C") (pintype "passive"))
      (node (ref "D54") (pin "C") (pinfunction "C_C") (pintype "passive"))
      (node (ref "D70") (pin "C") (pinfunction "C_C") (pintype "passive"))
      (node (ref "ISP") (pin "1") (pinfunction "1_1") (pintype "bidirectional"))
    )
    (net (code "7") (name "C5") (class "Default")
      (node (ref "ATMEGA32U4-AU") (pin "28") (pinfunction "PB4_28") (pintype "bidirectional"))
      (node (ref "D22") (pin "C") (pinfunction "C_C") (pintype "passive"))
      (node (ref "D39") (pin "C") (pinfunction "C_C") (pintype "passive"))
      (node (ref "D5") (pin "C") (pinfunction "C_C") (pintype "passive"))
      (node (ref "D55") (pin "C") (pinfunction "C_C") (pintype "passive"))
      (node (ref "D71") (pin "C") (pinfunction "C_C") (pintype "passive"))
    )
    (net (code "8") (name "C6") (class "Default")
      (node (ref "ATMEGA32U4-AU") (pin "29") (pinfunction "PB5_29") (pintype "bidirectional"))
      (node (ref "D23") (pin "C") (pinfunction "C_C") (pintype "passive"))
      (node (ref "D40") (pin "C") (pinfunction "C_C") (pintype "passive"))
      (node (ref "D56") (pin "C") (pinfunction "C_C") (pintype "passive"))
      (node (ref "D6") (pin "C") (pinfunction "C_C") (pintype "passive"))
      (node (ref "D72") (pin "C") (pinfunction "C_C") (pintype "passive"))
    )
    (net (code "9") (name "C7") (class "Default")
      (node (ref "ATMEGA32U4-AU") (pin "30") (pinfunction "PB6_30") (pintype "bidirectional"))
      (node (ref "D24") (pin "C") (pinfunction "C_C") (pintype "passive"))
      (node (ref "D41") (pin "C") (pinfunction "C_C") (pintype "passive"))
      (node (ref "D57") (pin "C") (pinfunction "C_C") (pintype "passive"))
      (node (ref "D7") (pin "C") (pinfunction "C_C") (pintype "passive"))
      (node (ref "D73") (pin "C") (pinfunction "C_C") (pintype "passive"))
    )
    (net (code "10") (name "C8") (class "Default")
      (node (ref "ATMEGA32U4-AU") (pin "12") (pinfunction "PB7_12") (pintype "bidirectional"))
      (node (ref "D25") (pin "C") (pinfunction "C_C") (pintype "passive"))
      (node (ref "D42") (pin "C") (pinfunction "C_C") (pintype "passive"))
      (node (ref "D58") (pin "C") (pinfunction "C_C") (pintype "passive"))
      (node (ref "D74") (pin "C") (pinfunction "C_C") (pintype "passive"))
      (node (ref "D8") (pin "C") (pinfunction "C_C") (pintype "passive"))
    )
    (net (code "11") (name "C9") (class "Default")
      (node (ref "ATMEGA32U4-AU") (pin "31") (pinfunction "PC6_31") (pintype "bidirectional"))
      (node (ref "D26") (pin "C") (pinfunction "C_C") (pintype "passive"))
      (node (ref "D43") (pin "C") (pinfunction "C_C") (pintype "passive"))
      (node (ref "D59") (pin "C") (pinfunction "C_C") (pintype "passive"))
      (node (ref "D75") (pin "C") (pinfunction "C_C") (pintype "passive"))
      (node (ref "D9") (pin "C") (pinfunction "C_C") (pintype "passive"))
    )
    (net (code "12") (name "C10") (class "Default")
      (node (ref "ATMEGA32U4-AU") (pin "32") (pinfunction "PC7_32") (pintype "bidirectional"))
      (node (ref "D10") (pin "C") (pinfunction "C_C") (pintype "passive"))
      (node (ref "D27") (pin "C") (pinfunction "C_C") (pintype "passive"))
      (node (ref "D44") (pin "C") (pinfunction "C_C") (pintype "passive"))
      (node (ref "D60") (pin "C") (pinfunction "C_C") (pintype "passive"))
      (node (ref "D76") (pin "C") (pinfunction "C_C") (pintype "passive"))
    )
    (net (code "13") (name "C11") (class "Default")
      (node (ref "ATMEGA32U4-AU") (pin "18") (pinfunction "PD0_18") (pintype "bidirectional"))
      (node (ref "D11") (pin "C") (pinfunction "C_C") (pintype "passive"))
      (node (ref "D28") (pin "C") (pinfunction "C_C") (pintype "passive"))
      (node (ref "D45") (pin "C") (pinfunction "C_C") (pintype "passive"))
      (node (ref "D61") (pin "C") (pinfunction "C_C") (pintype "passive"))
      (node (ref "D77") (pin "C") (pinfunction "C_C") (pintype "passive"))
    )
    (net (code "14") (name "C12") (class "Default")
      (node (ref "ATMEGA32U4-AU") (pin "19") (pinfunction "PD1_19") (pintype "bidirectional"))
      (node (ref "D12") (pin "C") (pinfunction "C_C") (pintype "passive"))
      (node (ref "D29") (pin "C") (pinfunction "C_C") (pintype "passive"))
      (node (ref "D46") (pin "C") (pinfunction "C_C") (pintype "passive"))
      (node (ref "D62") (pin "C") (pinfunction "C_C") (pintype "passive"))
      (node (ref "D78") (pin "C") (pinfunction "C_C") (pintype "passive"))
    )
    (net (code "15") (name "C13") (class "Default")
      (node (ref "ATMEGA32U4-AU") (pin "20") (pinfunction "PD2_20") (pintype "bidirectional"))
      (node (ref "D13") (pin "C") (pinfunction "C_C") (pintype "passive"))
      (node (ref "D30") (pin "C") (pinfunction "C_C") (pintype "passive"))
      (node (ref "D47") (pin "C") (pinfunction "C_C") (pintype "passive"))
      (node (ref "D63") (pin "C") (pinfunction "C_C") (pintype "passive"))
      (node (ref "D79") (pin "C") (pinfunction "C_C") (pintype "passive"))
    )
    (net (code "16") (name "C14") (class "Default")
      (node (ref "ATMEGA32U4-AU") (pin "21") (pinfunction "PD3_21") (pintype "bidirectional"))
      (node (ref "D14") (pin "C") (pinfunction "C_C") (pintype "passive"))
      (node (ref "D31") (pin "C") (pinfunction "C_C") (pintype "passive"))
      (node (ref "D48") (pin "C") (pinfunction "C_C") (pintype "passive"))
      (node (ref "D64") (pin "C") (pinfunction "C_C") (pintype "passive"))
    )
    (net (code "17") (name "C15") (class "Default")
      (node (ref "ATMEGA32U4-AU") (pin "25") (pinfunction "PD4_25") (pintype "bidirectional"))
      (node (ref "D15") (pin "C") (pinfunction "C_C") (pintype "passive"))
      (node (ref "D32") (pin "C") (pinfunction "C_C") (pintype "passive"))
      (node (ref "D49") (pin "C") (pinfunction "C_C") (pintype "passive"))
      (node (ref "D65") (pin "C") (pinfunction "C_C") (pintype "passive"))
    )
    (net (code "18") (name "C16") (class "Default")
      (node (ref "ATMEGA32U4-AU") (pin "22") (pinfunction "PD5_22") (pintype "bidirectional"))
      (node (ref "D16") (pin "C") (pinfunction "C_C") (pintype "passive"))
      (node (ref "D33") (pin "C") (pinfunction "C_C") (pintype "passive"))
      (node (ref "D50") (pin "C") (pinfunction "C_C") (pintype "passive"))
      (node (ref "D66") (pin "C") (pinfunction "C_C") (pintype "passive"))
    )
    (net (code "19") (name "C17") (class "Default")
      (node (ref "ATMEGA32U4-AU") (pin "27") (pinfunction "PD7_27") (pintype "bidirectional"))
      (node (ref "D17") (pin "C") (pinfunction "C_C") (pintype "passive"))
      (node (ref "D34") (pin "C") (pinfunction "C_C") (pintype "passive"))
    )
    (net (code "20") (name "Net-(ATMEGA32U4-AU-D+)") (class "Default")
      (node (ref "ATMEGA32U4-AU") (pin "4") (pinfunction "D+_4") (pintype "passive"))
      (node (ref "R2") (pin "2") (pinfunction "2_2") (pintype "passive"))
    )
    (net (code "21") (name "Net-(ATMEGA32U4-AU-D-)") (class "Default")
      (node (ref "ATMEGA32U4-AU") (pin "3") (pinfunction "D-_3") (pintype "passive"))
      (node (ref "R1") (pin "2") (pinfunction "2_2") (pintype "passive"))
    )
    (net (code "22") (name "Net-(ATMEGA32U4-AU-UCAP)") (class "Default")
      (node (ref "ATMEGA32U4-AU") (pin "6") (pinfunction "UCAP_6") (pintype "power_in"))
      (node (ref "C4") (pin "1") (pinfunction "1_1") (pintype "passive"))
    )
    (net (code "23") (name "Net-(ATMEGA32U4-AU-XTAL1)") (class "Default")
      (node (ref "ATMEGA32U4-AU") (pin "17") (pinfunction "XTAL1_17") (pintype "input"))
      (node (ref "C2") (pin "1") (pinfunction "1_1") (pintype "passive"))
      (node (ref "Y1") (pin "1") (pinfunction "1_1") (pintype "passive"))
    )
    (net (code "24") (name "Net-(ATMEGA32U4-AU-XTAL2)") (class "Default")
      (node (ref "ATMEGA32U4-AU") (pin "16") (pinfunction "XTAL2_16") (pintype "output"))
      (node (ref "C3") (pin "1") (pinfunction "1_1") (pintype "passive"))
      (node (ref "Y1") (pin "3") (pinfunction "2_3") (pintype "passive"))
    )
    (net (code "25") (name "Net-(ATMEGA32U4-AU-~{RESET})") (class "Default")
      (node (ref "ATMEGA32U4-AU") (pin "13") (pinfunction "~{RESET}_13") (pintype "input"))
      (node (ref "ISP") (pin "5") (pinfunction "5_5") (pintype "bidirectional"))
      (node (ref "S80") (pin "3") (pinfunction "2_3") (pintype "passive"))
    )
    (net (code "26") (name "Net-(S1-2)") (class "Default")
      (node (ref "D1") (pin "A") (pinfunction "A_A") (pintype "passive"))
      (node (ref "S1") (pin "S2") (pinfunction "2_S2") (pintype "passive"))
    )
    (net (code "27") (name "Net-(S2-2)") (class "Default")
      (node (ref "D2") (pin "A") (pinfunction "A_A") (pintype "passive"))
      (node (ref "S2") (pin "S2") (pinfunction "2_S2") (pintype "passive"))
    )
    (net (code "28") (name "Net-(S3-2)") (class "Default")
      (node (ref "D3") (pin "A") (pinfunction "A_A") (pintype "passive"))
      (node (ref "S3") (pin "S2") (pinfunction "2_S2") (pintype "passive"))
    )
    (net (code "29") (name "Net-(S4-2)") (class "Default")
      (node (ref "D4") (pin "A") (pinfunction "A_A") (pintype "passive"))
      (node (ref "S4") (pin "S2") (pinfunction "2_S2") (pintype "passive"))
    )
    (net (code "30") (name "Net-(S5-2)") (class "Default")
      (node (ref "D5") (pin "A") (pinfunction "A_A") (pintype "passive"))
      (node (ref "S5") (pin "S2") (pinfunction "2_S2") (pintype "passive"))
    )
    (net (code "31") (name "Net-(S6-2)") (class "Default")
      (node (ref "D6") (pin "A") (pinfunction "A_A") (pintype "passive"))
      (node (ref "S6") (pin "S2") (pinfunction "2_S2") (pintype "passive"))
    )
    (net (code "32") (name "Net-(S7-2)") (class "Default")
      (node (ref "D7") (pin "A") (pinfunction "A_A") (pintype "passive"))
      (node (ref "S7") (pin "S2") (pinfunction "2_S2") (pintype "passive"))
    )
    (net (code "33") (name "Net-(S8-2)") (class "Default")
      (node (ref "D8") (pin "A") (pinfunction "A_A") (pintype "passive"))
      (node (ref "S8") (pin "S2") (pinfunction "2_S2") (pintype "passive"))
    )
    (net (code "34") (name "Net-(S9-2)") (class "Default")
      (node (ref "D9") (pin "A") (pinfunction "A_A") (pintype "passive"))
      (node (ref "S9") (pin "S2") (pinfunction "2_S2") (pintype "passive"))
    )
    (net (code "35") (name "Net-(S10-2)") (class "Default")
      (node (ref "D10") (pin "A") (pinfunction "A_A") (pintype "passive"))
      (node (ref "S10") (pin "S2") (pinfunction "2_S2") (pintype "passive"))
    )
    (net (code "36") (name "Net-(S11-2)") (class "Default")
      (node (ref "D11") (pin "A") (pinfunction "A_A") (pintype "passive"))
      (node (ref "S11") (pin "S2") (pinfunction "2_S2") (pintype "passive"))
    )
    (net (code "37") (name "Net-(S12-2)") (class "Default")
      (node (ref "D12") (pin "A") (pinfunction "A_A") (pintype "passive"))
      (node (ref "S12") (pin "S2") (pinfunction "2_S2") (pintype "passive"))
    )
    (net (code "38") (name "Net-(S13-2)") (class "Default")
      (node (ref "D13") (pin "A") (pinfunction "A_A") (pintype "passive"))
      (node (ref "S13") (pin "S2") (pinfunction "2_S2") (pintype "passive"))
    )
    (net (code "39") (name "Net-(S14-2)") (class "Default")
      (node (ref "D14") (pin "A") (pinfunction "A_A") (pintype "passive"))
      (node (ref "S14") (pin "S2") (pinfunction "2_S2") (pintype "passive"))
    )
    (net (code "40") (name "Net-(S15-2)") (class "Default")
      (node (ref "D15") (pin "A") (pinfunction "A_A") (pintype "passive"))
      (node (ref "S15") (pin "S2") (pinfunction "2_S2") (pintype "passive"))
    )
    (net (code "41") (name "Net-(S16-2)") (class "Default")
      (node (ref "D16") (pin "A") (pinfunction "A_A") (pintype "passive"))
      (node (ref "S16") (pin "S2") (pinfunction "2_S2") (pintype "passive"))
    )
    (net (code "42") (name "Net-(S17-2)") (class "Default")
      (node (ref "D17") (pin "A") (pinfunction "A_A") (pintype "passive"))
      (node (ref "S17") (pin "S2") (pinfunction "2_S2") (pintype "passive"))
    )
    (net (code "43") (name "Net-(S18-2)") (class "Default")
      (node (ref "D18") (pin "A") (pinfunction "A_A") (pintype "passive"))
      (node (ref "S18") (pin "S2") (pinfunction "2_S2") (pintype "passive"))
    )
    (net (code "44") (name "Net-(S19-2)") (class "Default")
      (node (ref "D19") (pin "A") (pinfunction "A_A") (pintype "passive"))
      (node (ref "S19") (pin "S2") (pinfunction "2_S2") (pintype "passive"))
    )
    (net (code "45") (name "Net-(S20-2)") (class "Default")
      (node (ref "D20") (pin "A") (pinfunction "A_A") (pintype "passive"))
      (node (ref "S20") (pin "S2") (pinfunction "2_S2") (pintype "passive"))
    )
    (net (code "46") (name "Net-(S21-2)") (class "Default")
      (node (ref "D21") (pin "A") (pinfunction "A_A") (pintype "passive"))
      (node (ref "S21") (pin "S2") (pinfunction "2_S2") (pintype "passive"))
    )
    (net (code "47") (name "Net-(S22-2)") (class "Default")
      (node (ref "D22") (pin "A") (pinfunction "A_A") (pintype "passive"))
      (node (ref "S22") (pin "S2") (pinfunction "2_S2") (pintype "passive"))
    )
    (net (code "48") (name "Net-(S23-2)") (class "Default")
      (node (ref "D23") (pin "A") (pinfunction "A_A") (pintype "passive"))
      (node (ref "S23") (pin "S2") (pinfunction "2_S2") (pintype "passive"))
    )
    (net (code "49") (name "Net-(S24-2)") (class "Default")
      (node (ref "D24") (pin "A") (pinfunction "A_A") (pintype "passive"))
      (node (ref "S24") (pin "S2") (pinfunction "2_S2") (pintype "passive"))
    )
    (net (code "50") (name "Net-(S25-2)") (class "Default")
      (node (ref "D25") (pin "A") (pinfunction "A_A") (pintype "passive"))
      (node (ref "S25") (pin "S2") (pinfunction "2_S2") (pintype "passive"))
    )
    (net (code "51") (name "Net-(S26-2)") (class "Default")
      (node (ref "D26") (pin "A") (pinfunction "A_A") (pintype "passive"))
      (node (ref "S26") (pin "S2") (pinfunction "2_S2") (pintype "passive"))
    )
    (net (code "52") (name "Net-(S27-2)") (class "Default")
      (node (ref "D27") (pin "A") (pinfunction "A_A") (pintype "passive"))
      (node (ref "S27") (pin "S2") (pinfunction "2_S2") (pintype "passive"))
    )
    (net (code "53") (name "Net-(S28-2)") (class "Default")
      (node (ref "D28") (pin "A") (pinfunction "A_A") (pintype "passive"))
      (node (ref "S28") (pin "S2") (pinfunction "2_S2") (pintype "passive"))
    )
    (net (code "54") (name "Net-(S29-2)") (class "Default")
      (node (ref "D29") (pin "A") (pinfunction "A_A") (pintype "passive"))
      (node (ref "S29") (pin "S2") (pinfunction "2_S2") (pintype "passive"))
    )
    (net (code "55") (name "Net-(S30-2)") (class "Default")
      (node (ref "D30") (pin "A") (pinfunction "A_A") (pintype "passive"))
      (node (ref "S30") (pin "S2") (pinfunction "2_S2") (pintype "passive"))
    )
    (net (code "56") (name "Net-(S31-2)") (class "Default")
      (node (ref "D31") (pin "A") (pinfunction "A_A") (pintype "passive"))
      (node (ref "S31") (pin "S2") (pinfunction "2_S2") (pintype "passive"))
    )
    (net (code "57") (name "Net-(S32-2)") (class "Default")
      (node (ref "D32") (pin "A") (pinfunction "A_A") (pintype "passive"))
      (node (ref "S32") (pin "S2") (pinfunction "2_S2") (pintype "passive"))
    )
    (net (code "58") (name "Net-(S33-2)") (class "Default")
      (node (ref "D33") (pin "A") (pinfunction "A_A") (pintype "passive"))
      (node (ref "S33") (pin "S2") (pinfunction "2_S2") (pintype "passive"))
    )
    (net (code "59") (name "Net-(S34-2)") (class "Default")
      (node (ref "D34") (pin "A") (pinfunction "A_A") (pintype "passive"))
      (node (ref "S34") (pin "S2") (pinfunction "2_S2") (pintype "passive"))
    )
    (net (code "60") (name "Net-(S35-2)") (class "Default")
      (node (ref "D35") (pin "A") (pinfunction "A_A") (pintype "passive"))
      (node (ref "S35") (pin "S2") (pinfunction "2_S2") (pintype "passive"))
    )
    (net (code "61") (name "Net-(S36-2)") (class "Default")
      (node (ref "D36") (pin "A") (pinfunction "A_A") (pintype "passive"))
      (node (ref "S36") (pin "S2") (pinfunction "2_S2") (pintype "passive"))
    )
    (net (code "62") (name "Net-(S37-2)") (class "Default")
      (node (ref "D37") (pin "A") (pinfunction "A_A") (pintype "passive"))
      (node (ref "S37") (pin "S2") (pinfunction "2_S2") (pintype "passive"))
    )
    (net (code "63") (name "Net-(S38-2)") (class "Default")
      (node (ref "D38") (pin "A") (pinfunction "A_A") (pintype "passive"))
      (node (ref "S38") (pin "S2") (pinfunction "2_S2") (pintype "passive"))
    )
    (net (code "64") (name "Net-(S39-2)") (class "Default")
      (node (ref "D39") (pin "A") (pinfunction "A_A") (pintype "passive"))
      (node (ref "S39") (pin "S2") (pinfunction "2_S2") (pintype "passive"))
    )
    (net (code "65") (name "Net-(S40-2)") (class "Default")
      (node (ref "D40") (pin "A") (pinfunction "A_A") (pintype "passive"))
      (node (ref "S40") (pin "S2") (pinfunction "2_S2") (pintype "passive"))
    )
    (net (code "66") (name "Net-(S41-2)") (class "Default")
      (node (ref "D41") (pin "A") (pinfunction "A_A") (pintype "passive"))
      (node (ref "S41") (pin "S2") (pinfunction "2_S2") (pintype "passive"))
    )
    (net (code "67") (name "Net-(S42-2)") (class "Default")
      (node (ref "D42") (pin "A") (pinfunction "A_A") (pintype "passive"))
      (node (ref "S42") (pin "S2") (pinfunction "2_S2") (pintype "passive"))
    )
    (net (code "68") (name "Net-(S43-2)") (class "Default")
      (node (ref "D43") (pin "A") (pinfunction "A_A") (pintype "passive"))
      (node (ref "S43") (pin "S2") (pinfunction "2_S2") (pintype "passive"))
    )
    (net (code "69") (name "Net-(S44-2)") (class "Default")
      (node (ref "D44") (pin "A") (pinfunction "A_A") (pintype "passive"))
      (node (ref "S44") (pin "S2") (pinfunction "2_S2") (pintype "passive"))
    )
    (net (code "70") (name "Net-(S45-2)") (class "Default")
      (node (ref "D45") (pin "A") (pinfunction "A_A") (pintype "passive"))
      (node (ref "S45") (pin "S2") (pinfunction "2_S2") (pintype "passive"))
    )
    (net (code "71") (name "Net-(S46-2)") (class "Default")
      (node (ref "D46") (pin "A") (pinfunction "A_A") (pintype "passive"))
      (node (ref "S46") (pin "S2") (pinfunction "2_S2") (pintype "passive"))
    )
    (net (code "72") (name "Net-(S47-2)") (class "Default")
      (node (ref "D47") (pin "A") (pinfunction "A_A") (pintype "passive"))
      (node (ref "S47") (pin "S2") (pinfunction "2_S2") (pintype "passive"))
    )
    (net (code "73") (name "Net-(S48-2)") (class "Default")
      (node (ref "D48") (pin "A") (pinfunction "A_A") (pintype "passive"))
      (node (ref "S48") (pin "S2") (pinfunction "2_S2") (pintype "passive"))
    )
    (net (code "74") (name "Net-(S49-2)") (class "Default")
      (node (ref "D49") (pin "A") (pinfunction "A_A") (pintype "passive"))
      (node (ref "S49") (pin "S2") (pinfunction "2_S2") (pintype "passive"))
    )
    (net (code "75") (name "Net-(S50-2)") (class "Default")
      (node (ref "D50") (pin "A") (pinfunction "A_A") (pintype "passive"))
      (node (ref "S50") (pin "S2") (pinfunction "2_S2") (pintype "passive"))
    )
    (net (code "76") (name "Net-(S51-2)") (class "Default")
      (node (ref "D51") (pin "A") (pinfunction "A_A") (pintype "passive"))
      (node (ref "S51") (pin "S2") (pinfunction "2_S2") (pintype "passive"))
    )
    (net (code "77") (name "Net-(S52-2)") (class "Default")
      (node (ref "D52") (pin "A") (pinfunction "A_A") (pintype "passive"))
      (node (ref "S52") (pin "S2") (pinfunction "2_S2") (pintype "passive"))
    )
    (net (code "78") (name "Net-(S53-2)") (class "Default")
      (node (ref "D53") (pin "A") (pinfunction "A_A") (pintype "passive"))
      (node (ref "S53") (pin "S2") (pinfunction "2_S2") (pintype "passive"))
    )
    (net (code "79") (name "Net-(S54-2)") (class "Default")
      (node (ref "D54") (pin "A") (pinfunction "A_A") (pintype "passive"))
      (node (ref "S54") (pin "S2") (pinfunction "2_S2") (pintype "passive"))
    )
    (net (code "80") (name "Net-(S55-2)") (class "Default")
      (node (ref "D55") (pin "A") (pinfunction "A_A") (pintype "passive"))
      (node (ref "S55") (pin "S2") (pinfunction "2_S2") (pintype "passive"))
    )
    (net (code "81") (name "Net-(S56-2)") (class "Default")
      (node (ref "D56") (pin "A") (pinfunction "A_A") (pintype "passive"))
      (node (ref "S56") (pin "S2") (pinfunction "2_S2") (pintype "passive"))
    )
    (net (code "82") (name "Net-(S57-2)") (class "Default")
      (node (ref "D57") (pin "A") (pinfunction "A_A") (pintype "passive"))
      (node (ref "S57") (pin "S2") (pinfunction "2_S2") (pintype "passive"))
    )
    (net (code "83") (name "Net-(S58-2)") (class "Default")
      (node (ref "D58") (pin "A") (pinfunction "A_A") (pintype "passive"))
      (node (ref "S58") (pin "S2") (pinfunction "2_S2") (pintype "passive"))
    )
    (net (code "84") (name "Net-(S59-2)") (class "Default")
      (node (ref "D59") (pin "A") (pinfunction "A_A") (pintype "passive"))
      (node (ref "S59") (pin "S2") (pinfunction "2_S2") (pintype "passive"))
    )
    (net (code "85") (name "Net-(S60-2)") (class "Default")
      (node (ref "D60") (pin "A") (pinfunction "A_A") (pintype "passive"))
      (node (ref "S60") (pin "S2") (pinfunction "2_S2") (pintype "passive"))
    )
    (net (code "86") (name "Net-(S61-2)") (class "Default")
      (node (ref "D61") (pin "A") (pinfunction "A_A") (pintype "passive"))
      (node (ref "S61") (pin "S2") (pinfunction "2_S2") (pintype "passive"))
    )
    (net (code "87") (name "Net-(S62-2)") (class "Default")
      (node (ref "D62") (pin "A") (pinfunction "A_A") (pintype "passive"))
      (node (ref "S62") (pin "S2") (pinfunction "2_S2") (pintype "passive"))
    )
    (net (code "88") (name "Net-(S63-2)") (class "Default")
      (node (ref "D63") (pin "A") (pinfunction "A_A") (pintype "passive"))
      (node (ref "S63") (pin "S2") (pinfunction "2_S2") (pintype "passive"))
    )
    (net (code "89") (name "Net-(S64-2)") (class "Default")
      (node (ref "D64") (pin "A") (pinfunction "A_A") (pintype "passive"))
      (node (ref "S64") (pin "S2") (pinfunction "2_S2") (pintype "passive"))
    )
    (net (code "90") (name "Net-(S65-2)") (class "Default")
      (node (ref "D65") (pin "A") (pinfunction "A_A") (pintype "passive"))
      (node (ref "S65") (pin "S2") (pinfunction "2_S2") (pintype "passive"))
    )
    (net (code "91") (name "Net-(S66-2)") (class "Default")
      (node (ref "D66") (pin "A") (pinfunction "A_A") (pintype "passive"))
      (node (ref "S66") (pin "S2") (pinfunction "2_S2") (pintype "passive"))
    )
    (net (code "92") (name "Net-(S67-2)") (class "Default")
      (node (ref "D67") (pin "A") (pinfunction "A_A") (pintype "passive"))
      (node (ref "S67") (pin "S2") (pinfunction "2_S2") (pintype "passive"))
    )
    (net (code "93") (name "Net-(S68-2)") (class "Default")
      (node (ref "D68") (pin "A") (pinfunction "A_A") (pintype "passive"))
      (node (ref "S68") (pin "S2") (pinfunction "2_S2") (pintype "passive"))
    )
    (net (code "94") (name "Net-(S69-2)") (class "Default")
      (node (ref "D69") (pin "A") (pinfunction "A_A") (pintype "passive"))
      (node (ref "S69") (pin "S2") (pinfunction "2_S2") (pintype "passive"))
    )
    (net (code "95") (name "Net-(S70-2)") (class "Default")
      (node (ref "D70") (pin "A") (pinfunction "A_A") (pintype "passive"))
      (node (ref "S70") (pin "S2") (pinfunction "2_S2") (pintype "passive"))
    )
    (net (code "96") (name "Net-(S71-2)") (class "Default")
      (node (ref "D71") (pin "A") (pinfunction "A_A") (pintype "passive"))
      (node (ref "S71") (pin "S2") (pinfunction "2_S2") (pintype "passive"))
    )
    (net (code "97") (name "Net-(S72-2)") (class "Default")
      (node (ref "D72") (pin "A") (pinfunction "A_A") (pintype "passive"))
      (node (ref "S72") (pin "S2") (pinfunction "2_S2") (pintype "passive"))
    )
    (net (code "98") (name "Net-(S73-2)") (class "Default")
      (node (ref "D73") (pin "A") (pinfunction "A_A") (pintype "passive"))
      (node (ref "S73") (pin "S2") (pinfunction "2_S2") (pintype "passive"))
    )
    (net (code "99") (name "Net-(S74-2)") (class "Default")
      (node (ref "D74") (pin "A") (pinfunction "A_A") (pintype "passive"))
      (node (ref "S74") (pin "S2") (pinfunction "2_S2") (pintype "passive"))
    )
    (net (code "100") (name "Net-(S75-2)") (class "Default")
      (node (ref "D75") (pin "A") (pinfunction "A_A") (pintype "passive"))
      (node (ref "S75") (pin "S2") (pinfunction "2_S2") (pintype "passive"))
    )
    (net (code "101") (name "Net-(S76-2)") (class "Default")
      (node (ref "D76") (pin "A") (pinfunction "A_A") (pintype "passive"))
      (node (ref "S76") (pin "S2") (pinfunction "2_S2") (pintype "passive"))
    )
    (net (code "102") (name "Net-(S77-2)") (class "Default")
      (node (ref "D77") (pin "A") (pinfunction "A_A") (pintype "passive"))
      (node (ref "S77") (pin "S2") (pinfunction "2_S2") (pintype "passive"))
    )
    (net (code "103") (name "Net-(S78-2)") (class "Default")
      (node (ref "D78") (pin "A") (pinfunction "A_A") (pintype "passive"))
      (node (ref "S78") (pin "S2") (pinfunction "2_S2") (pintype "passive"))
    )
    (net (code "104") (name "Net-(S79-2)") (class "Default")
      (node (ref "D79") (pin "A") (pinfunction "A_A") (pintype "passive"))
      (node (ref "S79") (pin "S2") (pinfunction "2_S2") (pintype "passive"))
    )
    (net (code "105") (name "Net-(U$1-A5CC1)") (class "Default")
      (node (ref "R3") (pin "1") (pinfunction "1_1") (pintype "passive"))
      (node (ref "U$1") (pin "A5") (pinfunction "A5CC1_A5") (pintype "bidirectional"))
    )
    (net (code "106") (name "Net-(U$1-A6DP1)") (class "Default")
      (node (ref "R2") (pin "1") (pinfunction "1_1") (pintype "passive"))
      (node (ref "U$1") (pin "A6") (pinfunction "A6DP1_A6") (pintype "bidirectional"))
      (node (ref "U$1") (pin "B6") (pinfunction "B6DP2_B6") (pintype "bidirectional"))
    )
    (net (code "107") (name "Net-(U$1-A7DN1)") (class "Default")
      (node (ref "R1") (pin "1") (pinfunction "1_1") (pintype "passive"))
      (node (ref "U$1") (pin "A7") (pinfunction "A7DN1_A7") (pintype "bidirectional"))
      (node (ref "U$1") (pin "B7") (pinfunction "B7DN2_B7") (pintype "bidirectional"))
    )
    (net (code "108") (name "Net-(U$1-B5CC2)") (class "Default")
      (node (ref "R4") (pin "1") (pinfunction "1_1") (pintype "passive"))
      (node (ref "U$1") (pin "B5") (pinfunction "B5CC2_B5") (pintype "bidirectional"))
    )
    (net (code "109") (name "R1") (class "Default")
      (node (ref "ATMEGA32U4-AU") (pin "41") (pinfunction "PF0_41") (pintype "bidirectional"))
      (node (ref "S1") (pin "S1") (pinfunction "1_S1") (pintype "passive"))
      (node (ref "S10") (pin "S1") (pinfunction "1_S1") (pintype "passive"))
      (node (ref "S11") (pin "S1") (pinfunction "1_S1") (pintype "passive"))
      (node (ref "S12") (pin "S1") (pinfunction "1_S1") (pintype "passive"))
      (node (ref "S13") (pin "S1") (pinfunction "1_S1") (pintype "passive"))
      (node (ref "S14") (pin "S1") (pinfunction "1_S1") (pintype "passive"))
      (node (ref "S15") (pin "S1") (pinfunction "1_S1") (pintype "passive"))
      (node (ref "S16") (pin "S1") (pinfunction "1_S1") (pintype "passive"))
      (node (ref "S17") (pin "S1") (pinfunction "1_S1") (pintype "passive"))
      (node (ref "S2") (pin "S1") (pinfunction "1_S1") (pintype "passive"))
      (node (ref "S3") (pin "S1") (pinfunction "1_S1") (pintype "passive"))
      (node (ref "S4") (pin "S1") (pinfunction "1_S1") (pintype "passive"))
      (node (ref "S5") (pin "S1") (pinfunction "1_S1") (pintype "passive"))
      (node (ref "S6") (pin "S1") (pinfunction "1_S1") (pintype "passive"))
      (node (ref "S7") (pin "S1") (pinfunction "1_S1") (pintype "passive"))
      (node (ref "S8") (pin "S1") (pinfunction "1_S1") (pintype "passive"))
      (node (ref "S9") (pin "S1") (pinfunction "1_S1") (pintype "passive"))
    )
    (net (code "110") (name "R2") (class "Default")
      (node (ref "ATMEGA32U4-AU") (pin "40") (pinfunction "PF1_40") (pintype "bidirectional"))
      (node (ref "S18") (pin "S1") (pinfunction "1_S1") (pintype "passive"))
      (node (ref "S19") (pin "S1") (pinfunction "1_S1") (pintype "passive"))
      (node (ref "S20") (pin "S1") (pinfunction "1_S1") (pintype "passive"))
      (node (ref "S21") (pin "S1") (pinfunction "1_S1") (pintype "passive"))
      (node (ref "S22") (pin "S1") (pinfunction "1_S1") (pintype "passive"))
      (node (ref "S23") (pin "S1") (pinfunction "1_S1") (pintype "passive"))
      (node (ref "S24") (pin "S1") (pinfunction "1_S1") (pintype "passive"))
      (node (ref "S25") (pin "S1") (pinfunction "1_S1") (pintype "passive"))
      (node (ref "S26") (pin "S1") (pinfunction "1_S1") (pintype "passive"))
      (node (ref "S27") (pin "S1") (pinfunction "1_S1") (pintype "passive"))
      (node (ref "S28") (pin "S1") (pinfunction "1_S1") (pintype "passive"))
      (node (ref "S29") (pin "S1") (pinfunction "1_S1") (pintype "passive"))
      (node (ref "S30") (pin "S1") (pinfunction "1_S1") (pintype "passive"))
      (node (ref "S31") (pin "S1") (pinfunction "1_S1") (pintype "passive"))
      (node (ref "S32") (pin "S1") (pinfunction "1_S1") (pintype "passive"))
      (node (ref "S33") (pin "S1") (pinfunction "1_S1") (pintype "passive"))
      (node (ref "S34") (pin "S1") (pinfunction "1_S1") (pintype "passive"))
    )
    (net (code "111") (name "R3") (class "Default")
      (node (ref "ATMEGA32U4-AU") (pin "39") (pinfunction "PF4_39") (pintype "bidirectional"))
      (node (ref "S35") (pin "S1") (pinfunction "1_S1") (pintype "passive"))
      (node (ref "S36") (pin "S1") (pinfunction "1_S1") (pintype "passive"))
      (node (ref "S37") (pin "S1") (pinfunction "1_S1") (pintype "passive"))
      (node (ref "S38") (pin "S1") (pinfunction "1_S1") (pintype "passive"))
      (node (ref "S39") (pin "S1") (pinfunction "1_S1") (pintype "passive"))
      (node (ref "S40") (pin "S1") (pinfunction "1_S1") (pintype "passive"))
      (node (ref "S41") (pin "S1") (pinfunction "1_S1") (pintype "passive"))
      (node (ref "S42") (pin "S1") (pinfunction "1_S1") (pintype "passive"))
      (node (ref "S43") (pin "S1") (pinfunction "1_S1") (pintype "passive"))
      (node (ref "S44") (pin "S1") (pinfunction "1_S1") (pintype "passive"))
      (node (ref "S45") (pin "S1") (pinfunction "1_S1") (pintype "passive"))
      (node (ref "S46") (pin "S1") (pinfunction "1_S1") (pintype "passive"))
      (node (ref "S47") (pin "S1") (pinfunction "1_S1") (pintype "passive"))
      (node (ref "S48") (pin "S1") (pinfunction "1_S1") (pintype "passive"))
      (node (ref "S49") (pin "S1") (pinfunction "1_S1") (pintype "passive"))
      (node (ref "S50") (pin "S1") (pinfunction "1_S1") (pintype "passive"))
    )
    (net (code "112") (name "R4") (class "Default")
      (node (ref "ATMEGA32U4-AU") (pin "38") (pinfunction "PF5_38") (pintype "bidirectional"))
      (node (ref "S51") (pin "S1") (pinfunction "1_S1") (pintype "passive"))
      (node (ref "S52") (pin "S1") (pinfunction "1_S1") (pintype "passive"))
      (node (ref "S53") (pin "S1") (pinfunction "1_S1") (pintype "passive"))
      (node (ref "S54") (pin "S1") (pinfunction "1_S1") (pintype "passive"))
      (node (ref "S55") (pin "S1") (pinfunction "1_S1") (pintype "passive"))
      (node (ref "S56") (pin "S1") (pinfunction "1_S1") (pintype "passive"))
      (node (ref "S57") (pin "S1") (pinfunction "1_S1") (pintype "passive"))
      (node (ref "S58") (pin "S1") (pinfunction "1_S1") (pintype "passive"))
      (node (ref "S59") (pin "S1") (pinfunction "1_S1") (pintype "passive"))
      (node (ref "S60") (pin "S1") (pinfunction "1_S1") (pintype "passive"))
      (node (ref "S61") (pin "S1") (pinfunction "1_S1") (pintype "passive"))
      (node (ref "S62") (pin "S1") (pinfunction "1_S1") (pintype "passive"))
      (node (ref "S63") (pin "S1") (pinfunction "1_S1") (pintype "passive"))
      (node (ref "S64") (pin "S1") (pinfunction "1_S1") (pintype "passive"))
      (node (ref "S65") (pin "S1") (pinfunction "1_S1") (pintype "passive"))
      (node (ref "S66") (pin "S1") (pinfunction "1_S1") (pintype "passive"))
    )
    (net (code "113") (name "R5") (class "Default")
      (node (ref "ATMEGA32U4-AU") (pin "37") (pinfunction "PF6_37") (pintype "bidirectional"))
      (node (ref "S67") (pin "S1") (pinfunction "1_S1") (pintype "passive"))
      (node (ref "S68") (pin "S1") (pinfunction "1_S1") (pintype "passive"))
      (node (ref "S69") (pin "S1") (pinfunction "1_S1") (pintype "passive"))
      (node (ref "S70") (pin "S1") (pinfunction "1_S1") (pintype "passive"))
      (node (ref "S71") (pin "S1") (pinfunction "1_S1") (pintype "passive"))
      (node (ref "S72") (pin "S1") (pinfunction "1_S1") (pintype "passive"))
      (node (ref "S73") (pin "S1") (pinfunction "1_S1") (pintype "passive"))
      (node (ref "S74") (pin "S1") (pinfunction "1_S1") (pintype "passive"))
      (node (ref "S75") (pin "S1") (pinfunction "1_S1") (pintype "passive"))
      (node (ref "S76") (pin "S1") (pinfunction "1_S1") (pintype "passive"))
      (node (ref "S77") (pin "S1") (pinfunction "1_S1") (pintype "passive"))
      (node (ref "S78") (pin "S1") (pinfunction "1_S1") (pintype "passive"))
      (node (ref "S79") (pin "S1") (pinfunction "1_S1") (pintype "passive"))
    )
    (net (code "114") (name "unconnected-(ATMEGA32U4-AU-AREF-Pad42)") (class "Default")
      (node (ref "ATMEGA32U4-AU") (pin "42") (pinfunction "AREF_42") (pintype "input"))
    )
    (net (code "115") (name "unconnected-(ATMEGA32U4-AU-PD6-Pad26)") (class "Default")
      (node (ref "ATMEGA32U4-AU") (pin "26") (pinfunction "PD6_26") (pintype "bidirectional"))
    )
    (net (code "116") (name "unconnected-(ATMEGA32U4-AU-PE2-Pad33)") (class "Default")
      (node (ref "ATMEGA32U4-AU") (pin "33") (pinfunction "PE2_33") (pintype "bidirectional"))
    )
    (net (code "117") (name "unconnected-(ATMEGA32U4-AU-PE6-Pad1)") (class "Default")
      (node (ref "ATMEGA32U4-AU") (pin "1") (pinfunction "PE6_1") (pintype "bidirectional"))
    )
    (net (code "118") (name "unconnected-(ATMEGA32U4-AU-PF7-Pad36)") (class "Default")
      (node (ref "ATMEGA32U4-AU") (pin "36") (pinfunction "PF7_36") (pintype "bidirectional"))
    )
    (net (code "119") (name "unconnected-(S1-C-PadK)") (class "Default")
      (node (ref "S1") (pin "K") (pinfunction "C_K") (pintype "passive"))
    )
    (net (code "120") (name "unconnected-(S1-PadA)") (class "Default")
      (node (ref "S1") (pin "A") (pinfunction "A_A") (pintype "passive"))
    )
    (net (code "121") (name "unconnected-(S2-C-PadK)") (class "Default")
      (node (ref "S2") (pin "K") (pinfunction "C_K") (pintype "passive"))
    )
    (net (code "122") (name "unconnected-(S2-PadA)") (class "Default")
      (node (ref "S2") (pin "A") (pinfunction "A_A") (pintype "passive"))
    )
    (net (code "123") (name "unconnected-(S3-C-PadK)") (class "Default")
      (node (ref "S3") (pin "K") (pinfunction "C_K") (pintype "passive"))
    )
    (net (code "124") (name "unconnected-(S3-PadA)") (class "Default")
      (node (ref "S3") (pin "A") (pinfunction "A_A") (pintype "passive"))
    )
    (net (code "125") (name "unconnected-(S4-C-PadK)") (class "Default")
      (node (ref "S4") (pin "K") (pinfunction "C_K") (pintype "passive"))
    )
    (net (code "126") (name "unconnected-(S4-PadA)") (class "Default")
      (node (ref "S4") (pin "A") (pinfunction "A_A") (pintype "passive"))
    )
    (net (code "127") (name "unconnected-(S5-C-PadK)") (class "Default")
      (node (ref "S5") (pin "K") (pinfunction "C_K") (pintype "passive"))
    )
    (net (code "128") (name "unconnected-(S5-PadA)") (class "Default")
      (node (ref "S5") (pin "A") (pinfunction "A_A") (pintype "passive"))
    )
    (net (code "129") (name "unconnected-(S6-C-PadK)") (class "Default")
      (node (ref "S6") (pin "K") (pinfunction "C_K") (pintype "passive"))
    )
    (net (code "130") (name "unconnected-(S6-PadA)") (class "Default")
      (node (ref "S6") (pin "A") (pinfunction "A_A") (pintype "passive"))
    )
    (net (code "131") (name "unconnected-(S7-C-PadK)") (class "Default")
      (node (ref "S7") (pin "K") (pinfunction "C_K") (pintype "passive"))
    )
    (net (code "132") (name "unconnected-(S7-PadA)") (class "Default")
      (node (ref "S7") (pin "A") (pinfunction "A_A") (pintype "passive"))
    )
    (net (code "133") (name "unconnected-(S8-C-PadK)") (class "Default")
      (node (ref "S8") (pin "K") (pinfunction "C_K") (pintype "passive"))
    )
    (net (code "134") (name "unconnected-(S8-PadA)") (class "Default")
      (node (ref "S8") (pin "A") (pinfunction "A_A") (pintype "passive"))
    )
    (net (code "135") (name "unconnected-(S9-C-PadK)") (class "Default")
      (node (ref "S9") (pin "K") (pinfunction "C_K") (pintype "passive"))
    )
    (net (code "136") (name "unconnected-(S9-PadA)") (class "Default")
      (node (ref "S9") (pin "A") (pinfunction "A_A") (pintype "passive"))
    )
    (net (code "137") (name "unconnected-(S10-C-PadK)") (class "Default")
      (node (ref "S10") (pin "K") (pinfunction "C_K") (pintype "passive"))
    )
    (net (code "138") (name "unconnected-(S10-PadA)") (class "Default")
      (node (ref "S10") (pin "A") (pinfunction "A_A") (pintype "passive"))
    )
    (net (code "139") (name "unconnected-(S11-C-PadK)") (class "Default")
      (node (ref "S11") (pin "K") (pinfunction "C_K") (pintype "passive"))
    )
    (net (code "140") (name "unconnected-(S11-PadA)") (class "Default")
      (node (ref "S11") (pin "A") (pinfunction "A_A") (pintype "passive"))
    )
    (net (code "141") (name "unconnected-(S12-C-PadK)") (class "Default")
      (node (ref "S12") (pin "K") (pinfunction "C_K") (pintype "passive"))
    )
    (net (code "142") (name "unconnected-(S12-PadA)") (class "Default")
      (node (ref "S12") (pin "A") (pinfunction "A_A") (pintype "passive"))
    )
    (net (code "143") (name "unconnected-(S13-C-PadK)") (class "Default")
      (node (ref "S13") (pin "K") (pinfunction "C_K") (pintype "passive"))
    )
    (net (code "144") (name "unconnected-(S13-PadA)") (class "Default")
      (node (ref "S13") (pin "A") (pinfunction "A_A") (pintype "passive"))
    )
    (net (code "145") (name "unconnected-(S14-C-PadK)") (class "Default")
      (node (ref "S14") (pin "K") (pinfunction "C_K") (pintype "passive"))
    )
    (net (code "146") (name "unconnected-(S14-PadA)") (class "Default")
      (node (ref "S14") (pin "A") (pinfunction "A_A") (pintype "passive"))
    )
    (net (code "147") (name "unconnected-(S15-C-PadK)") (class "Default")
      (node (ref "S15") (pin "K") (pinfunction "C_K") (pintype "passive"))
    )
    (net (code "148") (name "unconnected-(S15-PadA)") (class "Default")
      (node (ref "S15") (pin "A") (pinfunction "A_A") (pintype "passive"))
    )
    (net (code "149") (name "unconnected-(S16-C-PadK)") (class "Default")
      (node (ref "S16") (pin "K") (pinfunction "C_K") (pintype "passive"))
    )
    (net (code "150") (name "unconnected-(S16-PadA)") (class "Default")
      (node (ref "S16") (pin "A") (pinfunction "A_A") (pintype "passive"))
    )
    (net (code "151") (name "unconnected-(S17-C-PadK)") (class "Default")
      (node (ref "S17") (pin "K") (pinfunction "C_K") (pintype "passive"))
    )
    (net (code "152") (name "unconnected-(S17-PadA)") (class "Default")
      (node (ref "S17") (pin "A") (pinfunction "A_A") (pintype "passive"))
    )
    (net (code "153") (name "unconnected-(S18-C-PadK)") (class "Default")
      (node (ref "S18") (pin "K") (pinfunction "C_K") (pintype "passive"))
    )
    (net (code "154") (name "unconnected-(S18-PadA)") (class "Default")
      (node (ref "S18") (pin "A") (pinfunction "A_A") (pintype "passive"))
    )
    (net (code "155") (name "unconnected-(S19-C-PadK)") (class "Default")
      (node (ref "S19") (pin "K") (pinfunction "C_K") (pintype "passive"))
    )
    (net (code "156") (name "unconnected-(S19-PadA)") (class "Default")
      (node (ref "S19") (pin "A") (pinfunction "A_A") (pintype "passive"))
    )
    (net (code "157") (name "unconnected-(S20-C-PadK)") (class "Default")
      (node (ref "S20") (pin "K") (pinfunction "C_K") (pintype "passive"))
    )
    (net (code "158") (name "unconnected-(S20-PadA)") (class "Default")
      (node (ref "S20") (pin "A") (pinfunction "A_A") (pintype "passive"))
    )
    (net (code "159") (name "unconnected-(S21-C-PadK)") (class "Default")
      (node (ref "S21") (pin "K") (pinfunction "C_K") (pintype "passive"))
    )
    (net (code "160") (name "unconnected-(S21-PadA)") (class "Default")
      (node (ref "S21") (pin "A") (pinfunction "A_A") (pintype "passive"))
    )
    (net (code "161") (name "unconnected-(S22-C-PadK)") (class "Default")
      (node (ref "S22") (pin "K") (pinfunction "C_K") (pintype "passive"))
    )
    (net (code "162") (name "unconnected-(S22-PadA)") (class "Default")
      (node (ref "S22") (pin "A") (pinfunction "A_A") (pintype "passive"))
    )
    (net (code "163") (name "unconnected-(S23-C-PadK)") (class "Default")
      (node (ref "S23") (pin "K") (pinfunction "C_K") (pintype "passive"))
    )
    (net (code "164") (name "unconnected-(S23-PadA)") (class "Default")
      (node (ref "S23") (pin "A") (pinfunction "A_A") (pintype "passive"))
    )
    (net (code "165") (name "unconnected-(S24-C-PadK)") (class "Default")
      (node (ref "S24") (pin "K") (pinfunction "C_K") (pintype "passive"))
    )
    (net (code "166") (name "unconnected-(S24-PadA)") (class "Default")
      (node (ref "S24") (pin "A") (pinfunction "A_A") (pintype "passive"))
    )
    (net (code "167") (name "unconnected-(S25-C-PadK)") (class "Default")
      (node (ref "S25") (pin "K") (pinfunction "C_K") (pintype "passive"))
    )
    (net (code "168") (name "unconnected-(S25-PadA)") (class "Default")
      (node (ref "S25") (pin "A") (pinfunction "A_A") (pintype "passive"))
    )
    (net (code "169") (name "unconnected-(S26-C-PadK)") (class "Default")
      (node (ref "S26") (pin "K") (pinfunction "C_K") (pintype "passive"))
    )
    (net (code "170") (name "unconnected-(S26-PadA)") (class "Default")
      (node (ref "S26") (pin "A") (pinfunction "A_A") (pintype "passive"))
    )
    (net (code "171") (name "unconnected-(S27-C-PadK)") (class "Default")
      (node (ref "S27") (pin "K") (pinfunction "C_K") (pintype "passive"))
    )
    (net (code "172") (name "unconnected-(S27-PadA)") (class "Default")
      (node (ref "S27") (pin "A") (pinfunction "A_A") (pintype "passive"))
    )
    (net (code "173") (name "unconnected-(S28-C-PadK)") (class "Default")
      (node (ref "S28") (pin "K") (pinfunction "C_K") (pintype "passive"))
    )
    (net (code "174") (name "unconnected-(S28-PadA)") (class "Default")
      (node (ref "S28") (pin "A") (pinfunction "A_A") (pintype "passive"))
    )
    (net (code "175") (name "unconnected-(S29-C-PadK)") (class "Default")
      (node (ref "S29") (pin "K") (pinfunction "C_K") (pintype "passive"))
    )
    (net (code "176") (name "unconnected-(S29-PadA)") (class "Default")
      (node (ref "S29") (pin "A") (pinfunction "A_A") (pintype "passive"))
    )
    (net (code "177") (name "unconnected-(S30-C-PadK)") (class "Default")
      (node (ref "S30") (pin "K") (pinfunction "C_K") (pintype "passive"))
    )
    (net (code "178") (name "unconnected-(S30-PadA)") (class "Default")
      (node (ref "S30") (pin "A") (pinfunction "A_A") (pintype "passive"))
    )
    (net (code "179") (name "unconnected-(S31-C-PadK)") (class "Default")
      (node (ref "S31") (pin "K") (pinfunction "C_K") (pintype "passive"))
    )
    (net (code "180") (name "unconnected-(S31-PadA)") (class "Default")
      (node (ref "S31") (pin "A") (pinfunction "A_A") (pintype "passive"))
    )
    (net (code "181") (name "unconnected-(S32-C-PadK)") (class "Default")
      (node (ref "S32") (pin "K") (pinfunction "C_K") (pintype "passive"))
    )
    (net (code "182") (name "unconnected-(S32-PadA)") (class "Default")
      (node (ref "S32") (pin "A") (pinfunction "A_A") (pintype "passive"))
    )
    (net (code "183") (name "unconnected-(S33-C-PadK)") (class "Default")
      (node (ref "S33") (pin "K") (pinfunction "C_K") (pintype "passive"))
    )
    (net (code "184") (name "unconnected-(S33-PadA)") (class "Default")
      (node (ref "S33") (pin "A") (pinfunction "A_A") (pintype "passive"))
    )
    (net (code "185") (name "unconnected-(S34-C-PadK)") (class "Default")
      (node (ref "S34") (pin "K") (pinfunction "C_K") (pintype "passive"))
    )
    (net (code "186") (name "unconnected-(S34-PadA)") (class "Default")
      (node (ref "S34") (pin "A") (pinfunction "A_A") (pintype "passive"))
    )
    (net (code "187") (name "unconnected-(S35-C-PadK)") (class "Default")
      (node (ref "S35") (pin "K") (pinfunction "C_K") (pintype "passive"))
    )
    (net (code "188") (name "unconnected-(S35-PadA)") (class "Default")
      (node (ref "S35") (pin "A") (pinfunction "A_A") (pintype "passive"))
    )
    (net (code "189") (name "unconnected-(S36-C-PadK)") (class "Default")
      (node (ref "S36") (pin "K") (pinfunction "C_K") (pintype "passive"))
    )
    (net (code "190") (name "unconnected-(S36-PadA)") (class "Default")
      (node (ref "S36") (pin "A") (pinfunction "A_A") (pintype "passive"))
    )
    (net (code "191") (name "unconnected-(S37-C-PadK)") (class "Default")
      (node (ref "S37") (pin "K") (pinfunction "C_K") (pintype "passive"))
    )
    (net (code "192") (name "unconnected-(S37-PadA)") (class "Default")
      (node (ref "S37") (pin "A") (pinfunction "A_A") (pintype "passive"))
    )
    (net (code "193") (name "unconnected-(S38-C-PadK)") (class "Default")
      (node (ref "S38") (pin "K") (pinfunction "C_K") (pintype "passive"))
    )
    (net (code "194") (name "unconnected-(S38-PadA)") (class "Default")
      (node (ref "S38") (pin "A") (pinfunction "A_A") (pintype "passive"))
    )
    (net (code "195") (name "unconnected-(S39-C-PadK)") (class "Default")
      (node (ref "S39") (pin "K") (pinfunction "C_K") (pintype "passive"))
    )
    (net (code "196") (name "unconnected-(S39-PadA)") (class "Default")
      (node (ref "S39") (pin "A") (pinfunction "A_A") (pintype "passive"))
    )
    (net (code "197") (name "unconnected-(S40-C-PadK)") (class "Default")
      (node (ref "S40") (pin "K") (pinfunction "C_K") (pintype "passive"))
    )
    (net (code "198") (name "unconnected-(S40-PadA)") (class "Default")
      (node (ref "S40") (pin "A") (pinfunction "A_A") (pintype "passive"))
    )
    (net (code "199") (name "unconnected-(S41-C-PadK)") (class "Default")
      (node (ref "S41") (pin "K") (pinfunction "C_K") (pintype "passive"))
    )
    (net (code "200") (name "unconnected-(S41-PadA)") (class "Default")
      (node (ref "S41") (pin "A") (pinfunction "A_A") (pintype "passive"))
    )
    (net (code "201") (name "unconnected-(S42-C-PadK)") (class "Default")
      (node (ref "S42") (pin "K") (pinfunction "C_K") (pintype "passive"))
    )
    (net (code "202") (name "unconnected-(S42-PadA)") (class "Default")
      (node (ref "S42") (pin "A") (pinfunction "A_A") (pintype "passive"))
    )
    (net (code "203") (name "unconnected-(S43-C-PadK)") (class "Default")
      (node (ref "S43") (pin "K") (pinfunction "C_K") (pintype "passive"))
    )
    (net (code "204") (name "unconnected-(S43-PadA)") (class "Default")
      (node (ref "S43") (pin "A") (pinfunction "A_A") (pintype "passive"))
    )
    (net (code "205") (name "unconnected-(S44-C-PadK)") (class "Default")
      (node (ref "S44") (pin "K") (pinfunction "C_K") (pintype "passive"))
    )
    (net (code "206") (name "unconnected-(S44-PadA)") (class "Default")
      (node (ref "S44") (pin "A") (pinfunction "A_A") (pintype "passive"))
    )
    (net (code "207") (name "unconnected-(S45-C-PadK)") (class "Default")
      (node (ref "S45") (pin "K") (pinfunction "C_K") (pintype "passive"))
    )
    (net (code "208") (name "unconnected-(S45-PadA)") (class "Default")
      (node (ref "S45") (pin "A") (pinfunction "A_A") (pintype "passive"))
    )
    (net (code "209") (name "unconnected-(S46-C-PadK)") (class "Default")
      (node (ref "S46") (pin "K") (pinfunction "C_K") (pintype "passive"))
    )
    (net (code "210") (name "unconnected-(S46-PadA)") (class "Default")
      (node (ref "S46") (pin "A") (pinfunction "A_A") (pintype "passive"))
    )
    (net (code "211") (name "unconnected-(S47-C-PadK)") (class "Default")
      (node (ref "S47") (pin "K") (pinfunction "C_K") (pintype "passive"))
    )
    (net (code "212") (name "unconnected-(S47-PadA)") (class "Default")
      (node (ref "S47") (pin "A") (pinfunction "A_A") (pintype "passive"))
    )
    (net (code "213") (name "unconnected-(S48-C-PadK)") (class "Default")
      (node (ref "S48") (pin "K") (pinfunction "C_K") (pintype "passive"))
    )
    (net (code "214") (name "unconnected-(S48-PadA)") (class "Default")
      (node (ref "S48") (pin "A") (pinfunction "A_A") (pintype "passive"))
    )
    (net (code "215") (name "unconnected-(S49-C-PadK)") (class "Default")
      (node (ref "S49") (pin "K") (pinfunction "C_K") (pintype "passive"))
    )
    (net (code "216") (name "unconnected-(S49-PadA)") (class "Default")
      (node (ref "S49") (pin "A") (pinfunction "A_A") (pintype "passive"))
    )
    (net (code "217") (name "unconnected-(S50-C-PadK)") (class "Default")
      (node (ref "S50") (pin "K") (pinfunction "C_K") (pintype "passive"))
    )
    (net (code "218") (name "unconnected-(S50-PadA)") (class "Default")
      (node (ref "S50") (pin "A") (pinfunction "A_A") (pintype "passive"))
    )
    (net (code "219") (name "unconnected-(S51-C-PadK)") (class "Default")
      (node (ref "S51") (pin "K") (pinfunction "C_K") (pintype "passive"))
    )
    (net (code "220") (name "unconnected-(S51-PadA)") (class "Default")
      (node (ref "S51") (pin "A") (pinfunction "A_A") (pintype "passive"))
    )
    (net (code "221") (name "unconnected-(S52-C-PadK)") (class "Default")
      (node (ref "S52") (pin "K") (pinfunction "C_K") (pintype "passive"))
    )
    (net (code "222") (name "unconnected-(S52-PadA)") (class "Default")
      (node (ref "S52") (pin "A") (pinfunction "A_A") (pintype "passive"))
    )
    (net (code "223") (name "unconnected-(S53-C-PadK)") (class "Default")
      (node (ref "S53") (pin "K") (pinfunction "C_K") (pintype "passive"))
    )
    (net (code "224") (name "unconnected-(S53-PadA)") (class "Default")
      (node (ref "S53") (pin "A") (pinfunction "A_A") (pintype "passive"))
    )
    (net (code "225") (name "unconnected-(S54-C-PadK)") (class "Default")
      (node (ref "S54") (pin "K") (pinfunction "C_K") (pintype "passive"))
    )
    (net (code "226") (name "unconnected-(S54-PadA)") (class "Default")
      (node (ref "S54") (pin "A") (pinfunction "A_A") (pintype "passive"))
    )
    (net (code "227") (name "unconnected-(S55-C-PadK)") (class "Default")
      (node (ref "S55") (pin "K") (pinfunction "C_K") (pintype "passive"))
    )
    (net (code "228") (name "unconnected-(S55-PadA)") (class "Default")
      (node (ref "S55") (pin "A") (pinfunction "A_A") (pintype "passive"))
    )
    (net (code "229") (name "unconnected-(S56-C-PadK)") (class "Default")
      (node (ref "S56") (pin "K") (pinfunction "C_K") (pintype "passive"))
    )
    (net (code "230") (name "unconnected-(S56-PadA)") (class "Default")
      (node (ref "S56") (pin "A") (pinfunction "A_A") (pintype "passive"))
    )
    (net (code "231") (name "unconnected-(S57-C-PadK)") (class "Default")
      (node (ref "S57") (pin "K") (pinfunction "C_K") (pintype "passive"))
    )
    (net (code "232") (name "unconnected-(S57-PadA)") (class "Default")
      (node (ref "S57") (pin "A") (pinfunction "A_A") (pintype "passive"))
    )
    (net (code "233") (name "unconnected-(S58-C-PadK)") (class "Default")
      (node (ref "S58") (pin "K") (pinfunction "C_K") (pintype "passive"))
    )
    (net (code "234") (name "unconnected-(S58-PadA)") (class "Default")
      (node (ref "S58") (pin "A") (pinfunction "A_A") (pintype "passive"))
    )
    (net (code "235") (name "unconnected-(S59-C-PadK)") (class "Default")
      (node (ref "S59") (pin "K") (pinfunction "C_K") (pintype "passive"))
    )
    (net (code "236") (name "unconnected-(S59-PadA)") (class "Default")
      (node (ref "S59") (pin "A") (pinfunction "A_A") (pintype "passive"))
    )
    (net (code "237") (name "unconnected-(S60-C-PadK)") (class "Default")
      (node (ref "S60") (pin "K") (pinfunction "C_K") (pintype "passive"))
    )
    (net (code "238") (name "unconnected-(S60-PadA)") (class "Default")
      (node (ref "S60") (pin "A") (pinfunction "A_A") (pintype "passive"))
    )
    (net (code "239") (name "unconnected-(S61-C-PadK)") (class "Default")
      (node (ref "S61") (pin "K") (pinfunction "C_K") (pintype "passive"))
    )
    (net (code "240") (name "unconnected-(S61-PadA)") (class "Default")
      (node (ref "S61") (pin "A") (pinfunction "A_A") (pintype "passive"))
    )
    (net (code "241") (name "unconnected-(S62-C-PadK)") (class "Default")
      (node (ref "S62") (pin "K") (pinfunction "C_K") (pintype "passive"))
    )
    (net (code "242") (name "unconnected-(S62-PadA)") (class "Default")
      (node (ref "S62") (pin "A") (pinfunction "A_A") (pintype "passive"))
    )
    (net (code "243") (name "unconnected-(S63-C-PadK)") (class "Default")
      (node (ref "S63") (pin "K") (pinfunction "C_K") (pintype "passive"))
    )
    (net (code "244") (name "unconnected-(S63-PadA)") (class "Default")
      (node (ref "S63") (pin "A") (pinfunction "A_A") (pintype "passive"))
    )
    (net (code "245") (name "unconnected-(S64-C-PadK)") (class "Default")
      (node (ref "S64") (pin "K") (pinfunction "C_K") (pintype "passive"))
    )
    (net (code "246") (name "unconnected-(S64-PadA)") (class "Default")
      (node (ref "S64") (pin "A") (pinfunction "A_A") (pintype "passive"))
    )
    (net (code "247") (name "unconnected-(S65-C-PadK)") (class "Default")
      (node (ref "S65") (pin "K") (pinfunction "C_K") (pintype "passive"))
    )
    (net (code "248") (name "unconnected-(S65-PadA)") (class "Default")
      (node (ref "S65") (pin "A") (pinfunction "A_A") (pintype "passive"))
    )
    (net (code "249") (name "unconnected-(S66-C-PadK)") (class "Default")
      (node (ref "S66") (pin "K") (pinfunction "C_K") (pintype "passive"))
    )
    (net (code "250") (name "unconnected-(S66-PadA)") (class "Default")
      (node (ref "S66") (pin "A") (pinfunction "A_A") (pintype "passive"))
    )
    (net (code "251") (name "unconnected-(S67-C-PadK)") (class "Default")
      (node (ref "S67") (pin "K") (pinfunction "C_K") (pintype "passive"))
    )
    (net (code "252") (name "unconnected-(S67-PadA)") (class "Default")
      (node (ref "S67") (pin "A") (pinfunction "A_A") (pintype "passive"))
    )
    (net (code "253") (name "unconnected-(S68-C-PadK)") (class "Default")
      (node (ref "S68") (pin "K") (pinfunction "C_K") (pintype "passive"))
    )
    (net (code "254") (name "unconnected-(S68-PadA)") (class "Default")
      (node (ref "S68") (pin "A") (pinfunction "A_A") (pintype "passive"))
    )
    (net (code "255") (name "unconnected-(S69-C-PadK)") (class "Default")
      (node (ref "S69") (pin "K") (pinfunction "C_K") (pintype "passive"))
    )
    (net (code "256") (name "unconnected-(S69-PadA)") (class "Default")
      (node (ref "S69") (pin "A") (pinfunction "A_A") (pintype "passive"))
    )
    (net (code "257") (name "unconnected-(S70-C-PadK)") (class "Default")
      (node (ref "S70") (pin "K") (pinfunction "C_K") (pintype "passive"))
    )
    (net (code "258") (name "unconnected-(S70-PadA)") (class "Default")
      (node (ref "S70") (pin "A") (pinfunction "A_A") (pintype "passive"))
    )
    (net (code "259") (name "unconnected-(S71-C-PadK)") (class "Default")
      (node (ref "S71") (pin "K") (pinfunction "C_K") (pintype "passive"))
    )
    (net (code "260") (name "unconnected-(S71-PadA)") (class "Default")
      (node (ref "S71") (pin "A") (pinfunction "A_A") (pintype "passive"))
    )
    (net (code "261") (name "unconnected-(S72-C-PadK)") (class "Default")
      (node (ref "S72") (pin "K") (pinfunction "C_K") (pintype "passive"))
    )
    (net (code "262") (name "unconnected-(S72-PadA)") (class "Default")
      (node (ref "S72") (pin "A") (pinfunction "A_A") (pintype "passive"))
    )
    (net (code "263") (name "unconnected-(S73-C-PadK)") (class "Default")
      (node (ref "S73") (pin "K") (pinfunction "C_K") (pintype "passive"))
    )
    (net (code "264") (name "unconnected-(S73-PadA)") (class "Default")
      (node (ref "S73") (pin "A") (pinfunction "A_A") (pintype "passive"))
    )
    (net (code "265") (name "unconnected-(S74-C-PadK)") (class "Default")
      (node (ref "S74") (pin "K") (pinfunction "C_K") (pintype "passive"))
    )
    (net (code "266") (name "unconnected-(S74-PadA)") (class "Default")
      (node (ref "S74") (pin "A") (pinfunction "A_A") (pintype "passive"))
    )
    (net (code "267") (name "unconnected-(S75-C-PadK)") (class "Default")
      (node (ref "S75") (pin "K") (pinfunction "C_K") (pintype "passive"))
    )
    (net (code "268") (name "unconnected-(S75-PadA)") (class "Default")
      (node (ref "S75") (pin "A") (pinfunction "A_A") (pintype "passive"))
    )
    (net (code "269") (name "unconnected-(S76-C-PadK)") (class "Default")
      (node (ref "S76") (pin "K") (pinfunction "C_K") (pintype "passive"))
    )
    (net (code "270") (name "unconnected-(S76-PadA)") (class "Default")
      (node (ref "S76") (pin "A") (pinfunction "A_A") (pintype "passive"))
    )
    (net (code "271") (name "unconnected-(S77-C-PadK)") (class "Default")
      (node (ref "S77") (pin "K") (pinfunction "C_K") (pintype "passive"))
    )
    (net (code "272") (name "unconnected-(S77-PadA)") (class "Default")
      (node (ref "S77") (pin "A") (pinfunction "A_A") (pintype "passive"))
    )
    (net (code "273") (name "unconnected-(S78-C-PadK)") (class "Default")
      (node (ref "S78") (pin "K") (pinfunction "C_K") (pintype "passive"))
    )
    (net (code "274") (name "unconnected-(S78-PadA)") (class "Default")
      (node (ref "S78") (pin "A") (pinfunction "A_A") (pintype "passive"))
    )
    (net (code "275") (name "unconnected-(S79-C-PadK)") (class "Default")
      (node (ref "S79") (pin "K") (pinfunction "C_K") (pintype "passive"))
    )
    (net (code "276") (name "unconnected-(S79-PadA)") (class "Default")
      (node (ref "S79") (pin "A") (pinfunction "A_A") (pintype "passive"))
    )
    (net (code "277") (name "unconnected-(U$1-A8SBU1-PadA8)") (class "Default")
      (node (ref "U$1") (pin "A8") (pinfunction "A8SBU1_A8") (pintype "bidirectional"))
    )
    (net (code "278") (name "unconnected-(U$1-B8SBU2-PadB8)") (class "Default")
      (node (ref "U$1") (pin "B8") (pinfunction "B8SBU2_B8") (pintype "bidirectional"))
    )
  )
)
